# Base_Station_v3b.net
KiCad netlist of a schematic drawn in EAGLE
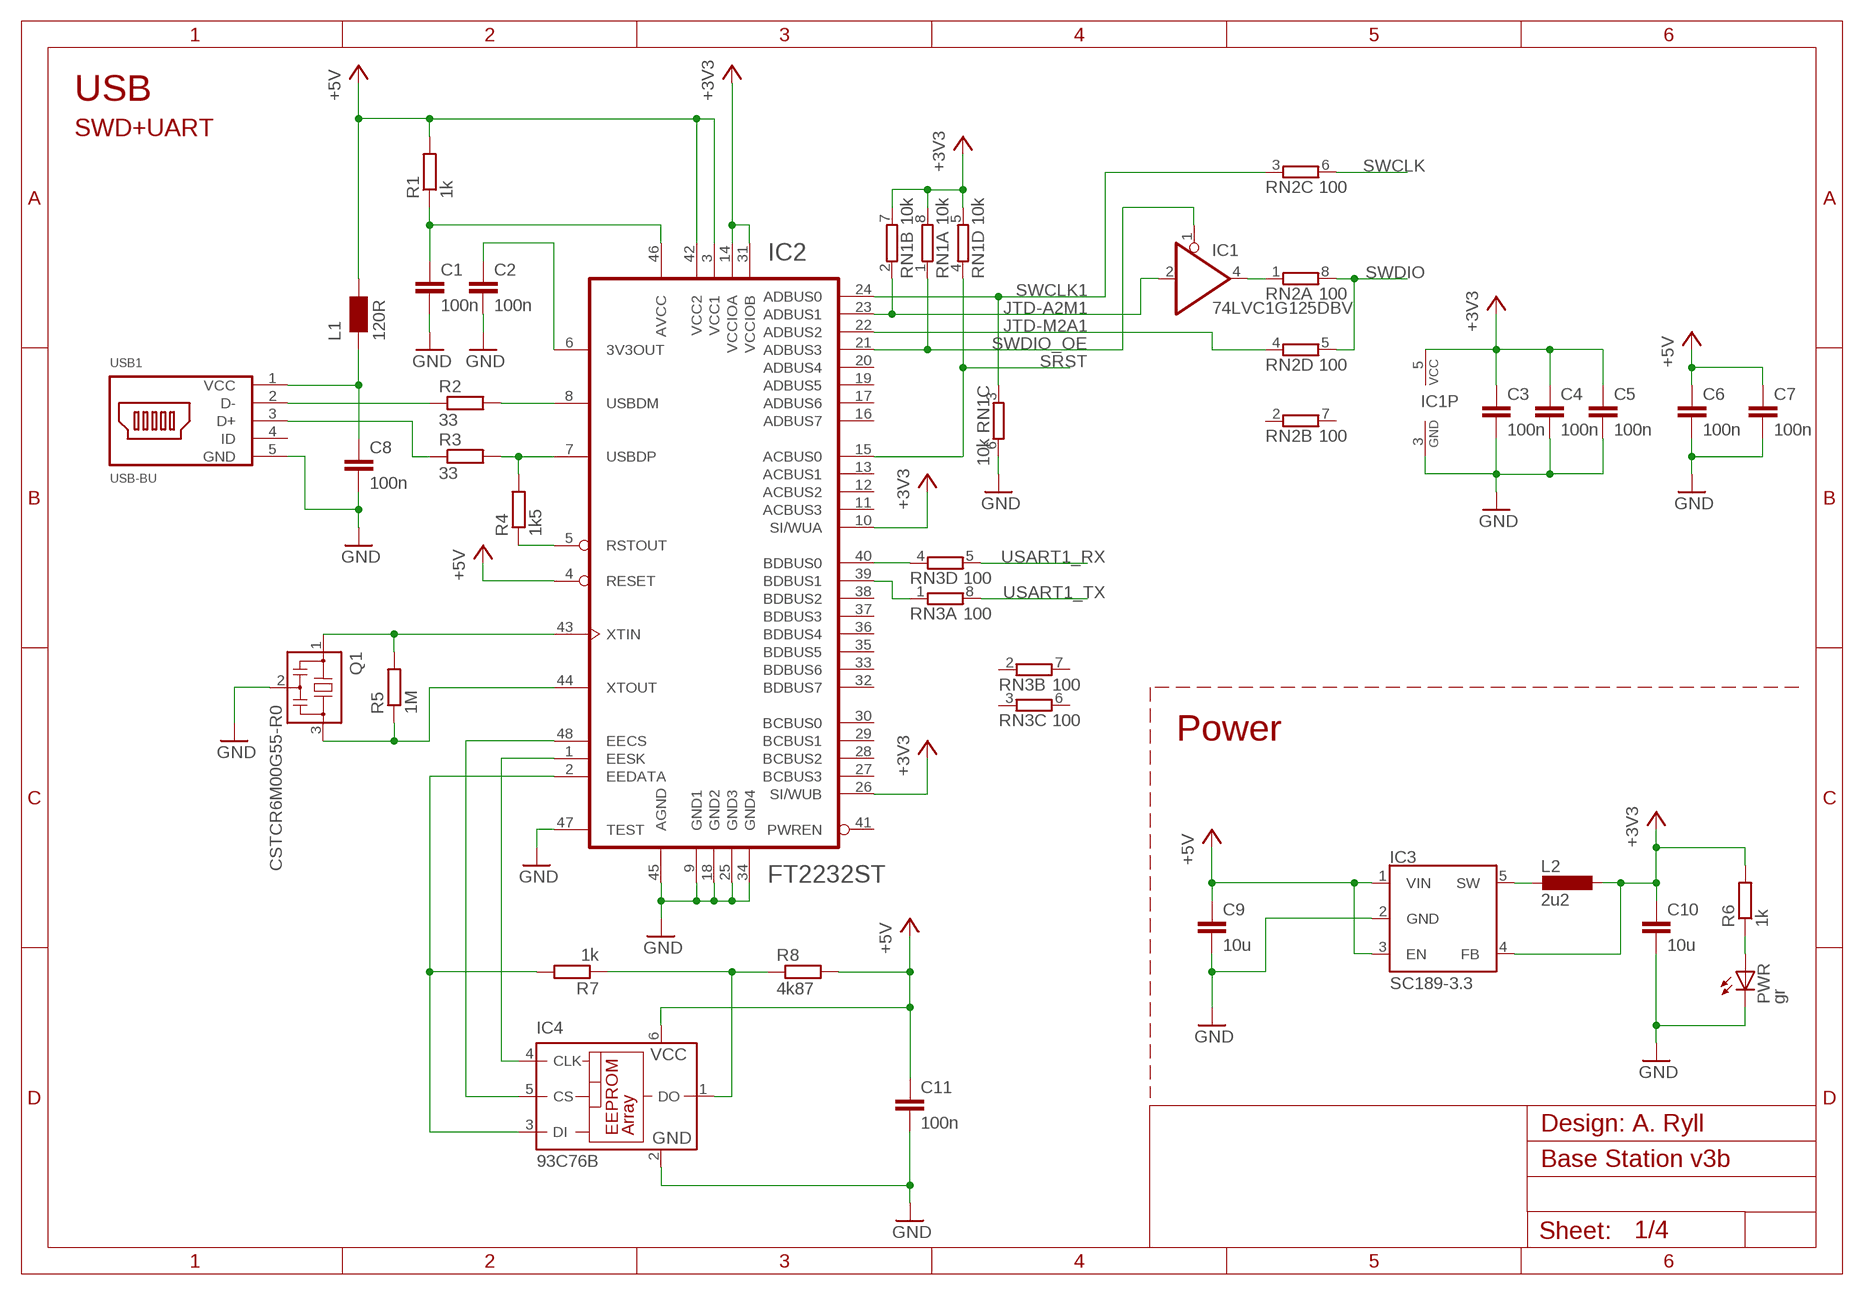
[diagram p0: schematic, sheet 1]
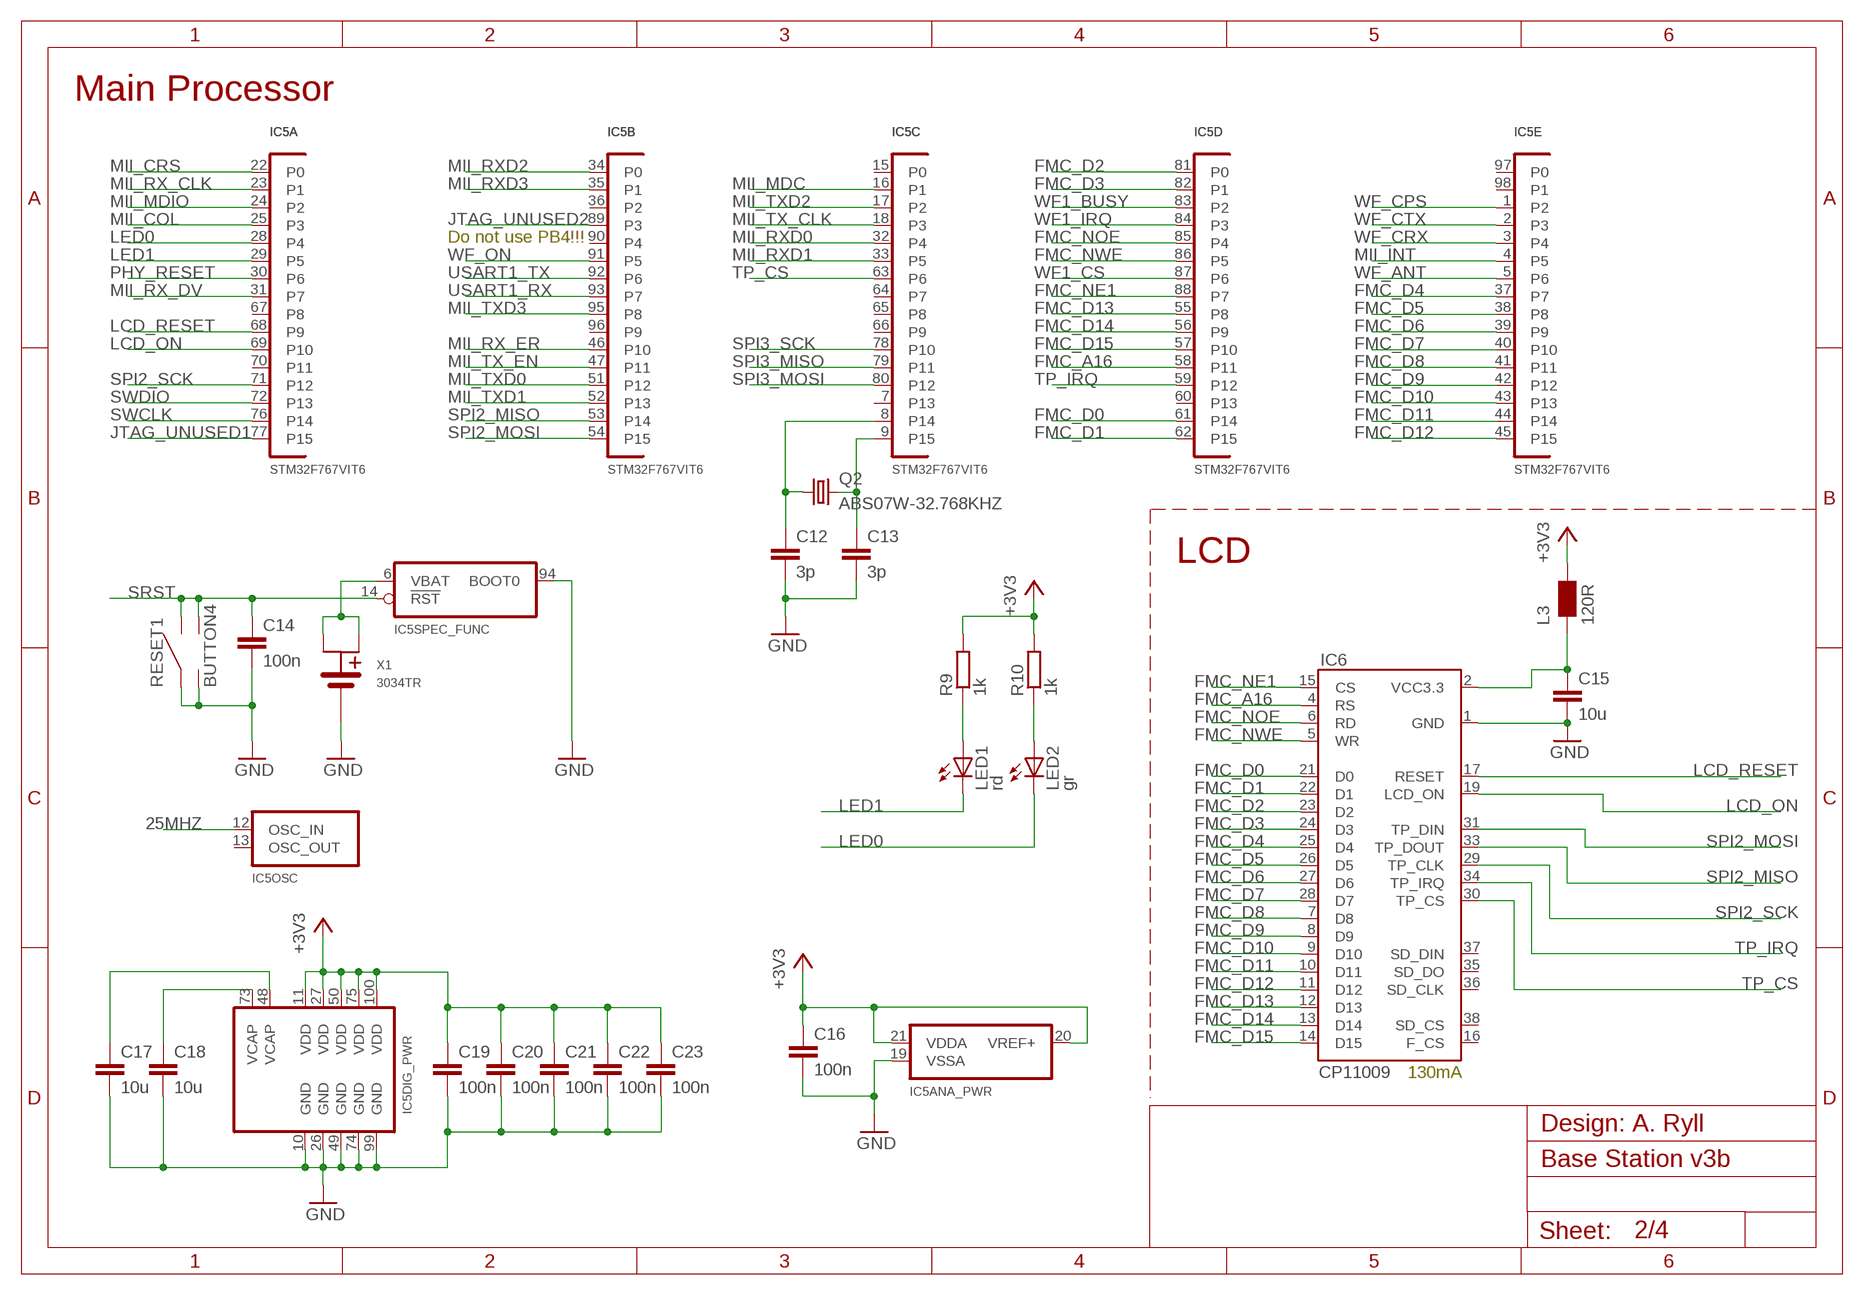
[diagram p1: schematic, sheet 2]
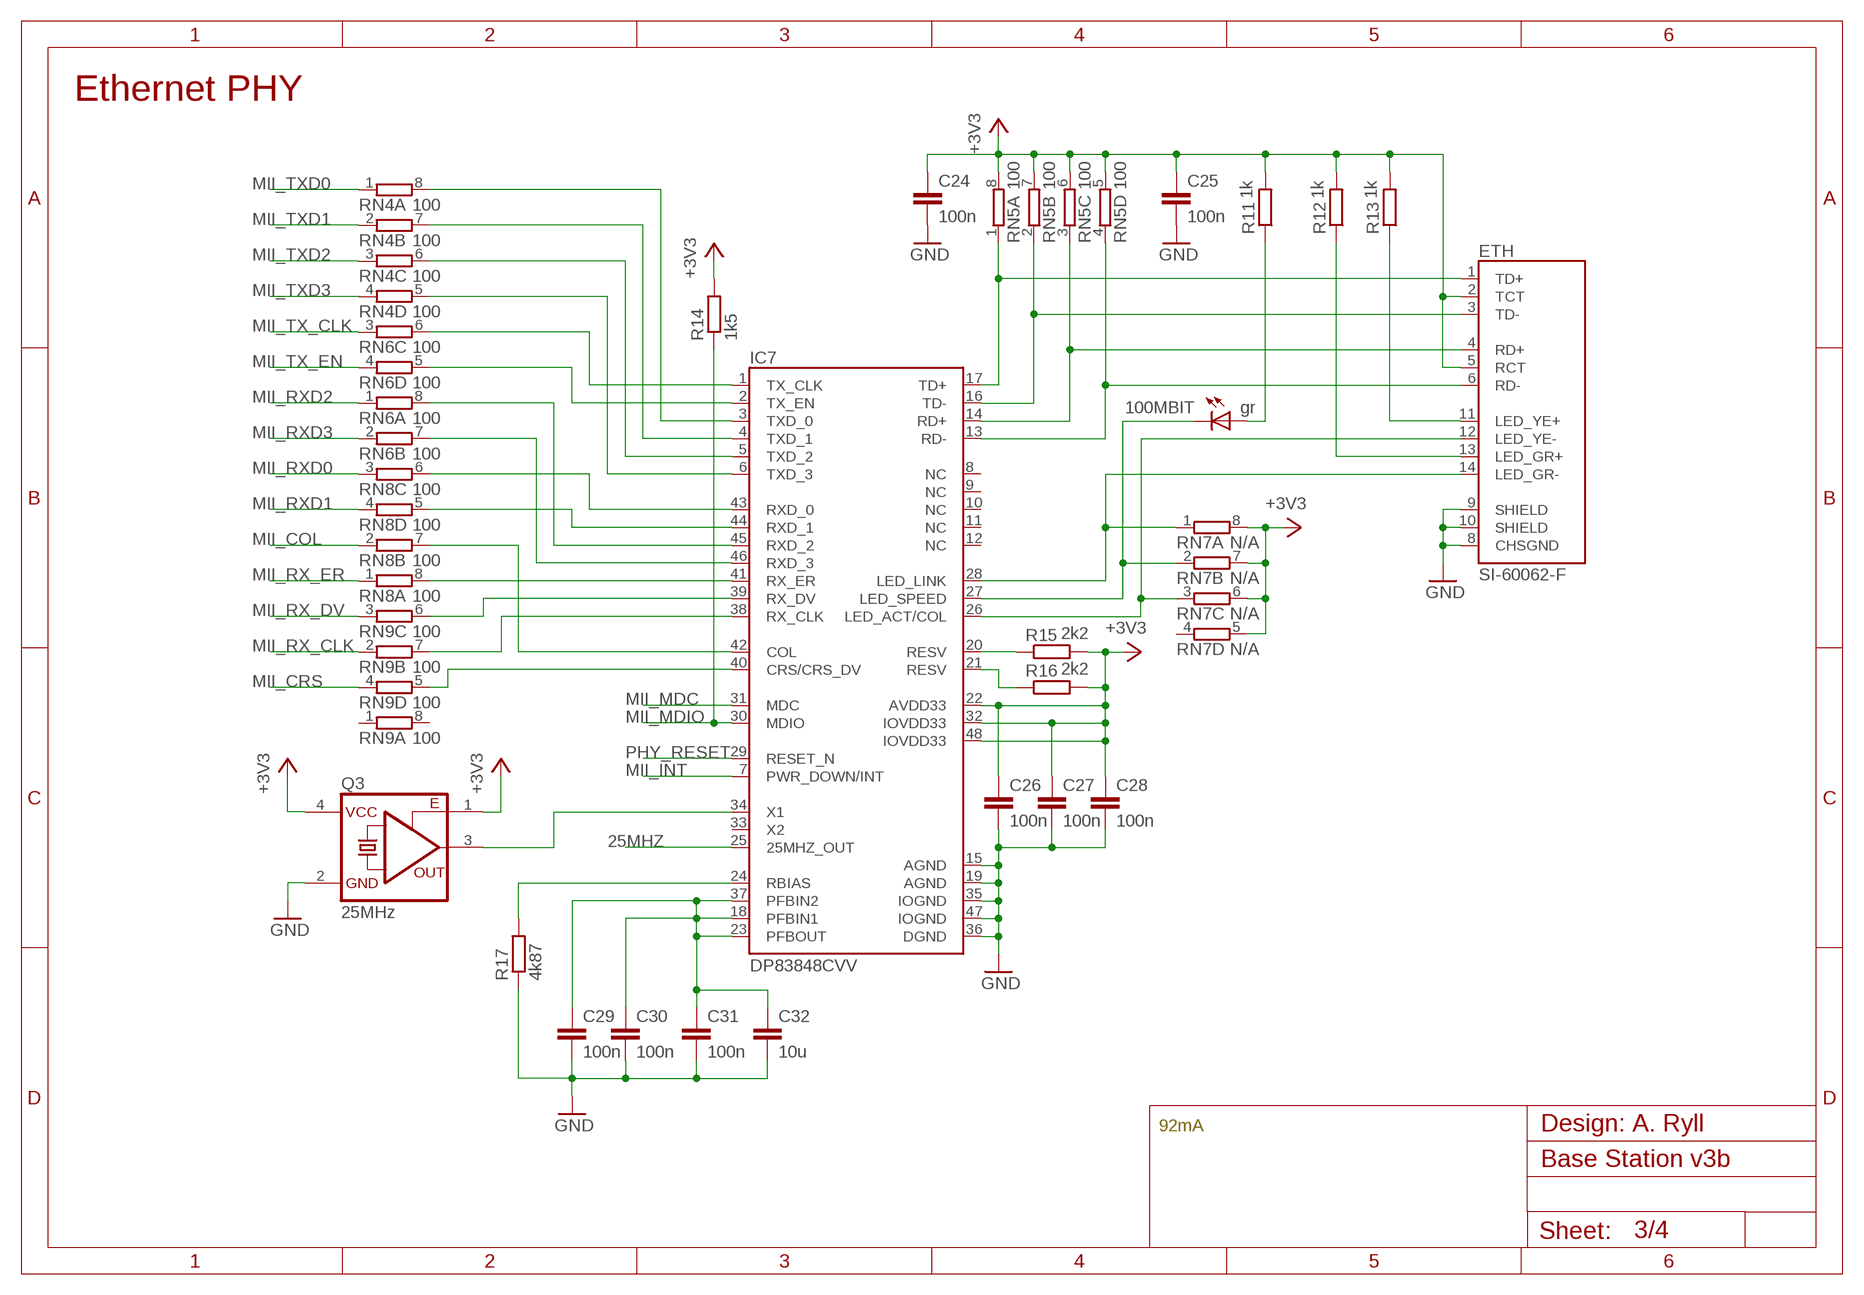
[diagram p2: schematic, sheet 3]
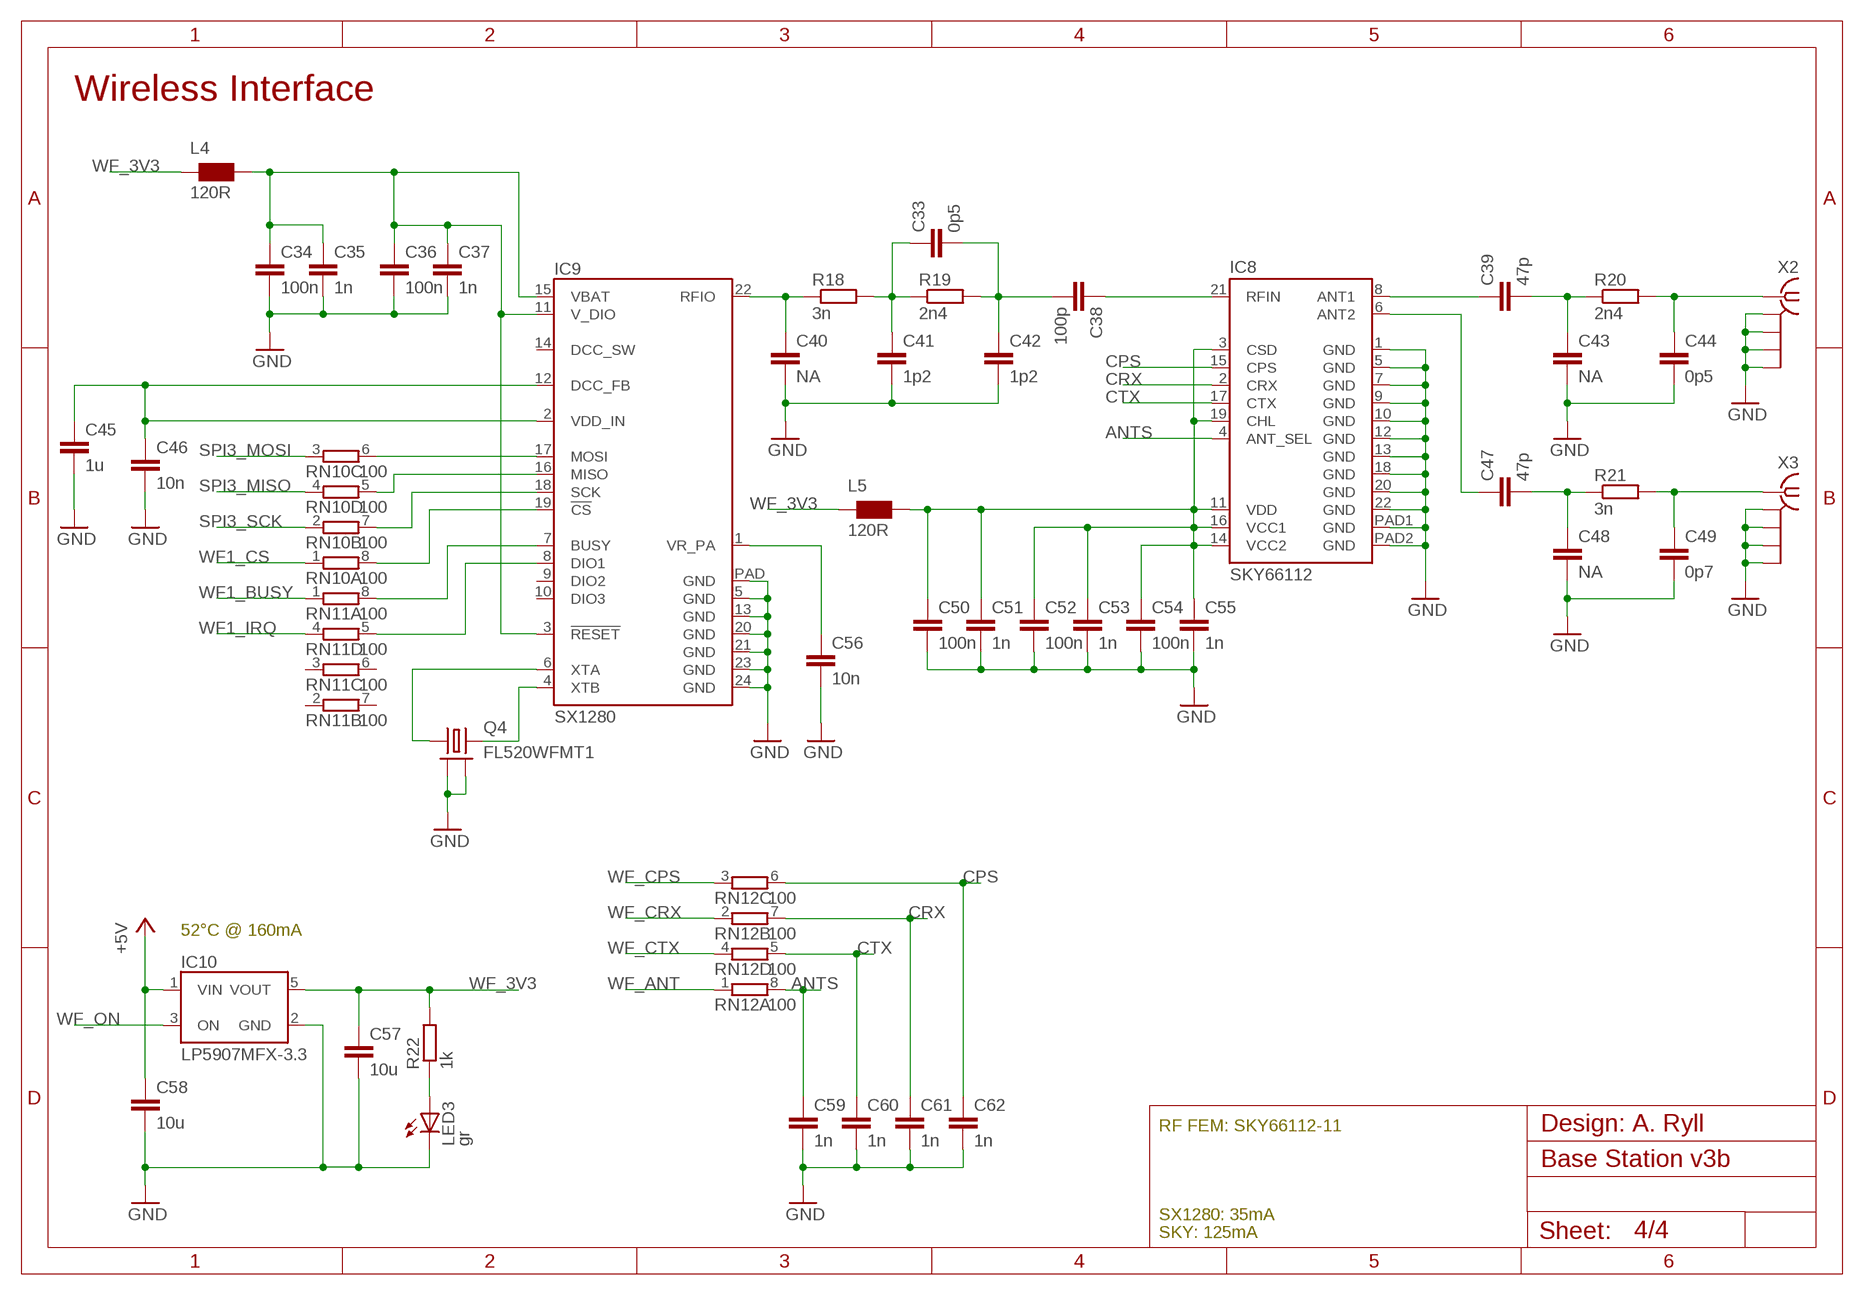
[diagram p3: schematic, sheet 4]

(export (version "E")
  (design (tool "Eeschema 10.0.6"))
  (components
    (comp (ref "C12")
      (value "3p")
      (footprint "eagle-import:C0603")
      (libsource (lib "eagle-import") (part "C-EUC0603"))
    )
    (comp (ref "C13")
      (value "3p")
      (footprint "eagle-import:C0603")
      (libsource (lib "eagle-import") (part "C-EUC0603"))
    )
    (comp (ref "C14")
      (value "100n")
      (footprint "eagle-import:C0603")
      (libsource (lib "eagle-import") (part "C-EUC0603"))
    )
    (comp (ref "C15")
      (value "10u")
      (footprint "eagle-import:C0603")
      (libsource (lib "eagle-import") (part "C-EUC0603"))
    )
    (comp (ref "C16")
      (value "100n")
      (footprint "eagle-import:C0603")
      (libsource (lib "eagle-import") (part "C-EUC0603"))
    )
    (comp (ref "C17")
      (value "10u")
      (footprint "eagle-import:C0603")
      (libsource (lib "eagle-import") (part "C-EUC0603"))
    )
    (comp (ref "C18")
      (value "10u")
      (footprint "eagle-import:C0603")
      (libsource (lib "eagle-import") (part "C-EUC0603"))
    )
    (comp (ref "C19")
      (value "100n")
      (footprint "eagle-import:C0603")
      (libsource (lib "eagle-import") (part "C-EUC0603"))
    )
    (comp (ref "C20")
      (value "100n")
      (footprint "eagle-import:C0603")
      (libsource (lib "eagle-import") (part "C-EUC0603"))
    )
    (comp (ref "C21")
      (value "100n")
      (footprint "eagle-import:C0603")
      (libsource (lib "eagle-import") (part "C-EUC0603"))
    )
    (comp (ref "C22")
      (value "100n")
      (footprint "eagle-import:C0603")
      (libsource (lib "eagle-import") (part "C-EUC0603"))
    )
    (comp (ref "C23")
      (value "100n")
      (footprint "eagle-import:C0603")
      (libsource (lib "eagle-import") (part "C-EUC0603"))
    )
    (comp (ref "IC5")
      (value "STM32F767VIT6")
      (footprint "eagle-import:LQFP100-ST")
      (libsource (lib "eagle-import") (part "STM32F76_V"))
    )
    (comp (ref "IC6")
      (value "CP11009")
      (footprint "eagle-import:CP11009-THX")
      (libsource (lib "eagle-import") (part "CP11009X"))
    )
    (comp (ref "L3")
      (value "120R")
      (footprint "eagle-import:0603")
      (libsource (lib "eagle-import") (part "WE-CBF_0603"))
    )
    (comp (ref "LED1")
      (value "rd")
      (footprint "eagle-import:CHIP-LED0603")
      (libsource (lib "eagle-import") (part "LEDCHIP-LED0603"))
    )
    (comp (ref "LED2")
      (value "gr")
      (footprint "eagle-import:CHIP-LED0603")
      (libsource (lib "eagle-import") (part "LEDCHIP-LED0603"))
    )
    (comp (ref "Q2")
      (value "ABS07W-32.768KHZ")
      (footprint "eagle-import:CRYSTAL-07W")
      (libsource (lib "eagle-import") (part "CRYSTAL07W"))
    )
    (comp (ref "R9")
      (value "1k")
      (footprint "eagle-import:R0603")
      (libsource (lib "eagle-import") (part "R-EU_R0603"))
    )
    (comp (ref "R10")
      (value "1k")
      (footprint "eagle-import:R0603")
      (libsource (lib "eagle-import") (part "R-EU_R0603"))
    )
    (comp (ref "RESET1")
      (value "BUTTON4")
      (footprint "eagle-import:BUTTON4")
      (libsource (lib "eagle-import") (part "BUTTON4"))
    )
    (comp (ref "X1")
      (value "3034TR")
      (footprint "eagle-import:CR2025")
      (libsource (lib "eagle-import") (part "BAT3"))
    )
    (comp (ref "C1")
      (value "100n")
      (footprint "eagle-import:C0603")
      (libsource (lib "eagle-import") (part "C-EUC0603"))
    )
    (comp (ref "C2")
      (value "100n")
      (footprint "eagle-import:C0603")
      (libsource (lib "eagle-import") (part "C-EUC0603"))
    )
    (comp (ref "C3")
      (value "100n")
      (footprint "eagle-import:C0603")
      (libsource (lib "eagle-import") (part "C-EUC0603"))
    )
    (comp (ref "C4")
      (value "100n")
      (footprint "eagle-import:C0603")
      (libsource (lib "eagle-import") (part "C-EUC0603"))
    )
    (comp (ref "C5")
      (value "100n")
      (footprint "eagle-import:C0603")
      (libsource (lib "eagle-import") (part "C-EUC0603"))
    )
    (comp (ref "C6")
      (value "100n")
      (footprint "eagle-import:C0603")
      (libsource (lib "eagle-import") (part "C-EUC0603"))
    )
    (comp (ref "C7")
      (value "100n")
      (footprint "eagle-import:C0603")
      (libsource (lib "eagle-import") (part "C-EUC0603"))
    )
    (comp (ref "C8")
      (value "100n")
      (footprint "eagle-import:C0603")
      (libsource (lib "eagle-import") (part "C-EUC0603"))
    )
    (comp (ref "C9")
      (value "10u")
      (footprint "eagle-import:C0603")
      (libsource (lib "eagle-import") (part "C-EUC0603"))
    )
    (comp (ref "C10")
      (value "10u")
      (footprint "eagle-import:C0603")
      (libsource (lib "eagle-import") (part "C-EUC0603"))
    )
    (comp (ref "C11")
      (value "100n")
      (footprint "eagle-import:C0603")
      (libsource (lib "eagle-import") (part "C-EUC0603"))
    )
    (comp (ref "IC1")
      (value "74LVC1G125DBV")
      (footprint "eagle-import:SOT23-5")
      (libsource (lib "eagle-import") (part "741G125DBVLVC"))
    )
    (comp (ref "IC2")
      (value "FT2232ST")
      (footprint "eagle-import:LQFP48-ST")
      (libsource (lib "eagle-import") (part "FT2232ST"))
    )
    (comp (ref "IC3")
      (value "SC189-3.3")
      (footprint "eagle-import:SOT23-5")
      (libsource (lib "eagle-import") (part "LM3671"))
    )
    (comp (ref "IC4")
      (value "93C76B")
      (footprint "eagle-import:SOT23-6")
      (libsource (lib "eagle-import") (part "9376?BC"))
    )
    (comp (ref "L1")
      (value "120R")
      (footprint "eagle-import:0603")
      (libsource (lib "eagle-import") (part "WE-CBF_0603"))
    )
    (comp (ref "L2")
      (value "2u2")
      (footprint "eagle-import:IHLP1616")
      (libsource (lib "eagle-import") (part "LIHLP"))
    )
    (comp (ref "PWR")
      (value "gr")
      (footprint "eagle-import:CHIP-LED0603")
      (libsource (lib "eagle-import") (part "LEDCHIP-LED0603"))
    )
    (comp (ref "Q1")
      (value "CSTCR6M00G55-R0")
      (footprint "eagle-import:CSTCR6M")
      (fields (field (name "MPN") "CSTCR6M00G53-R0"))
      (libsource (lib "eagle-import") (part "CSTCR6M00G53Z"))
    )
    (comp (ref "R1")
      (value "1k")
      (footprint "eagle-import:R0603")
      (libsource (lib "eagle-import") (part "R-EU_R0603"))
    )
    (comp (ref "R2")
      (value "33")
      (footprint "eagle-import:R0603")
      (libsource (lib "eagle-import") (part "R-EU_R0603"))
    )
    (comp (ref "R3")
      (value "33")
      (footprint "eagle-import:R0603")
      (libsource (lib "eagle-import") (part "R-EU_R0603"))
    )
    (comp (ref "R4")
      (value "1k5")
      (footprint "eagle-import:R0603")
      (libsource (lib "eagle-import") (part "R-EU_R0603"))
    )
    (comp (ref "R5")
      (value "1M")
      (footprint "eagle-import:R0603")
      (libsource (lib "eagle-import") (part "R-EU_R0603"))
    )
    (comp (ref "R6")
      (value "1k")
      (footprint "eagle-import:R0603")
      (libsource (lib "eagle-import") (part "R-EU_R0603"))
    )
    (comp (ref "R7")
      (value "1k")
      (footprint "eagle-import:R0603")
      (libsource (lib "eagle-import") (part "R-EU_R0603"))
    )
    (comp (ref "R8")
      (value "4k87")
      (footprint "eagle-import:R0603")
      (libsource (lib "eagle-import") (part "R-EU_R0603"))
    )
    (comp (ref "RN1")
      (value "10k")
      (footprint "eagle-import:EXB28V")
      (libsource (lib "eagle-import") (part "4R-NEXB28V"))
    )
    (comp (ref "RN2")
      (value "100")
      (footprint "eagle-import:EXB28V")
      (libsource (lib "eagle-import") (part "4R-NEXB28V"))
    )
    (comp (ref "RN3")
      (value "100")
      (footprint "eagle-import:EXB28V")
      (libsource (lib "eagle-import") (part "4R-NEXB28V"))
    )
    (comp (ref "USB1")
      (value "USB-BU")
      (footprint "eagle-import:USB-BMICRO")
      (libsource (lib "eagle-import") (part "USB-BU"))
    )
    (comp (ref "C33")
      (value "0p5")
      (footprint "eagle-import:C0402")
      (libsource (lib "eagle-import") (part "C-EUC0402"))
    )
    (comp (ref "C34")
      (value "100n")
      (footprint "eagle-import:C0603")
      (libsource (lib "eagle-import") (part "C-EUC0603"))
    )
    (comp (ref "C35")
      (value "1n")
      (footprint "eagle-import:C0603")
      (libsource (lib "eagle-import") (part "C-EUC0603"))
    )
    (comp (ref "C36")
      (value "100n")
      (footprint "eagle-import:C0603")
      (libsource (lib "eagle-import") (part "C-EUC0603"))
    )
    (comp (ref "C37")
      (value "1n")
      (footprint "eagle-import:C0603")
      (libsource (lib "eagle-import") (part "C-EUC0603"))
    )
    (comp (ref "C38")
      (value "100p")
      (footprint "eagle-import:C0402")
      (libsource (lib "eagle-import") (part "C-EUC0402"))
    )
    (comp (ref "C39")
      (value "47p")
      (footprint "eagle-import:C0402")
      (libsource (lib "eagle-import") (part "C-EUC0402"))
    )
    (comp (ref "C40")
      (value "NA")
      (footprint "eagle-import:C0402")
      (libsource (lib "eagle-import") (part "C-EUC0402"))
    )
    (comp (ref "C41")
      (value "1p2")
      (footprint "eagle-import:C0402")
      (libsource (lib "eagle-import") (part "C-EUC0402"))
    )
    (comp (ref "C42")
      (value "1p2")
      (footprint "eagle-import:C0402")
      (libsource (lib "eagle-import") (part "C-EUC0402"))
    )
    (comp (ref "C43")
      (value "NA")
      (footprint "eagle-import:C0402")
      (libsource (lib "eagle-import") (part "C-EUC0402"))
    )
    (comp (ref "C44")
      (value "0p5")
      (footprint "eagle-import:C0402")
      (libsource (lib "eagle-import") (part "C-EUC0402"))
    )
    (comp (ref "C45")
      (value "1u")
      (footprint "eagle-import:C0603")
      (libsource (lib "eagle-import") (part "C-EUC0603"))
    )
    (comp (ref "C46")
      (value "10n")
      (footprint "eagle-import:C0603")
      (libsource (lib "eagle-import") (part "C-EUC0603"))
    )
    (comp (ref "C47")
      (value "47p")
      (footprint "eagle-import:C0402")
      (libsource (lib "eagle-import") (part "C-EUC0402"))
    )
    (comp (ref "C48")
      (value "NA")
      (footprint "eagle-import:C0402")
      (libsource (lib "eagle-import") (part "C-EUC0402"))
    )
    (comp (ref "C49")
      (value "0p7")
      (footprint "eagle-import:C0402")
      (libsource (lib "eagle-import") (part "C-EUC0402"))
    )
    (comp (ref "C50")
      (value "100n")
      (footprint "eagle-import:C0603")
      (libsource (lib "eagle-import") (part "C-EUC0603"))
    )
    (comp (ref "C51")
      (value "1n")
      (footprint "eagle-import:C0603")
      (libsource (lib "eagle-import") (part "C-EUC0603"))
    )
    (comp (ref "C52")
      (value "100n")
      (footprint "eagle-import:C0603")
      (libsource (lib "eagle-import") (part "C-EUC0603"))
    )
    (comp (ref "C53")
      (value "1n")
      (footprint "eagle-import:C0603")
      (libsource (lib "eagle-import") (part "C-EUC0603"))
    )
    (comp (ref "C54")
      (value "100n")
      (footprint "eagle-import:C0603")
      (libsource (lib "eagle-import") (part "C-EUC0603"))
    )
    (comp (ref "C55")
      (value "1n")
      (footprint "eagle-import:C0603")
      (libsource (lib "eagle-import") (part "C-EUC0603"))
    )
    (comp (ref "C56")
      (value "10n")
      (footprint "eagle-import:C0603")
      (libsource (lib "eagle-import") (part "C-EUC0603"))
    )
    (comp (ref "C57")
      (value "10u")
      (footprint "eagle-import:C0603")
      (libsource (lib "eagle-import") (part "C-EUC0603"))
    )
    (comp (ref "C58")
      (value "10u")
      (footprint "eagle-import:C0603")
      (libsource (lib "eagle-import") (part "C-EUC0603"))
    )
    (comp (ref "C59")
      (value "1n")
      (footprint "eagle-import:C0603")
      (libsource (lib "eagle-import") (part "C-EUC0603"))
    )
    (comp (ref "C60")
      (value "1n")
      (footprint "eagle-import:C0603")
      (libsource (lib "eagle-import") (part "C-EUC0603"))
    )
    (comp (ref "C61")
      (value "1n")
      (footprint "eagle-import:C0603")
      (libsource (lib "eagle-import") (part "C-EUC0603"))
    )
    (comp (ref "C62")
      (value "1n")
      (footprint "eagle-import:C0603")
      (libsource (lib "eagle-import") (part "C-EUC0603"))
    )
    (comp (ref "IC8")
      (value "SKY66112")
      (footprint "eagle-import:SMCM-22")
      (libsource (lib "eagle-import") (part "SKY66112"))
    )
    (comp (ref "IC9")
      (value "SX1280")
      (footprint "eagle-import:QFN24L")
      (libsource (lib "eagle-import") (part "SX1280"))
    )
    (comp (ref "IC10")
      (value "LP5907MFX-3.3")
      (footprint "eagle-import:SOT23-5L")
      (libsource (lib "eagle-import") (part "LP2980"))
    )
    (comp (ref "L4")
      (value "120R")
      (footprint "eagle-import:0603")
      (libsource (lib "eagle-import") (part "WE-CBF_0603"))
    )
    (comp (ref "L5")
      (value "120R")
      (footprint "eagle-import:0603")
      (libsource (lib "eagle-import") (part "WE-CBF_0603"))
    )
    (comp (ref "LED3")
      (value "gr")
      (footprint "eagle-import:CHIP-LED0603")
      (libsource (lib "eagle-import") (part "LEDCHIP-LED0603"))
    )
    (comp (ref "Q4")
      (value "FL520WFMT1")
      (footprint "eagle-import:CRYSTAL-7M")
      (libsource (lib "eagle-import") (part "CRYSTAL47M"))
    )
    (comp (ref "R18")
      (value "3n")
      (footprint "eagle-import:R0402")
      (libsource (lib "eagle-import") (part "R-EU_R0402"))
    )
    (comp (ref "R19")
      (value "2n4")
      (footprint "eagle-import:R0402")
      (libsource (lib "eagle-import") (part "R-EU_R0402"))
    )
    (comp (ref "R20")
      (value "2n4")
      (footprint "eagle-import:R0402")
      (libsource (lib "eagle-import") (part "R-EU_R0402"))
    )
    (comp (ref "R21")
      (value "3n")
      (footprint "eagle-import:R0402")
      (libsource (lib "eagle-import") (part "R-EU_R0402"))
    )
    (comp (ref "R22")
      (value "1k")
      (footprint "eagle-import:R0603")
      (libsource (lib "eagle-import") (part "R-EU_R0603"))
    )
    (comp (ref "RN10")
      (value "100")
      (footprint "eagle-import:EXB28V")
      (libsource (lib "eagle-import") (part "4R-NEXB28V"))
    )
    (comp (ref "RN11")
      (value "100")
      (footprint "eagle-import:EXB28V")
      (libsource (lib "eagle-import") (part "4R-NEXB28V"))
    )
    (comp (ref "RN12")
      (value "100")
      (footprint "eagle-import:EXB28V")
      (libsource (lib "eagle-import") (part "4R-NEXB28V"))
    )
    (comp (ref "X2")
      (value "ANT-SMA-EDGERA")
      (footprint "eagle-import:ANT-SMA-RA")
      (libsource (lib "eagle-import") (part "ANT-SMA-EDGERA"))
    )
    (comp (ref "X3")
      (value "ANT-SMA-EDGERA")
      (footprint "eagle-import:ANT-SMA-RA")
      (libsource (lib "eagle-import") (part "ANT-SMA-EDGERA"))
    )
    (comp (ref "100MBIT")
      (value "gr")
      (footprint "eagle-import:CHIP-LED0603")
      (libsource (lib "eagle-import") (part "LEDCHIP-LED0603"))
    )
    (comp (ref "C24")
      (value "100n")
      (footprint "eagle-import:C0603")
      (libsource (lib "eagle-import") (part "C-EUC0603"))
    )
    (comp (ref "C25")
      (value "100n")
      (footprint "eagle-import:C0603")
      (libsource (lib "eagle-import") (part "C-EUC0603"))
    )
    (comp (ref "C26")
      (value "100n")
      (footprint "eagle-import:C0603")
      (libsource (lib "eagle-import") (part "C-EUC0603"))
    )
    (comp (ref "C27")
      (value "100n")
      (footprint "eagle-import:C0603")
      (libsource (lib "eagle-import") (part "C-EUC0603"))
    )
    (comp (ref "C28")
      (value "100n")
      (footprint "eagle-import:C0603")
      (libsource (lib "eagle-import") (part "C-EUC0603"))
    )
    (comp (ref "C29")
      (value "100n")
      (footprint "eagle-import:C0603")
      (libsource (lib "eagle-import") (part "C-EUC0603"))
    )
    (comp (ref "C30")
      (value "100n")
      (footprint "eagle-import:C0603")
      (libsource (lib "eagle-import") (part "C-EUC0603"))
    )
    (comp (ref "C31")
      (value "100n")
      (footprint "eagle-import:C0603")
      (libsource (lib "eagle-import") (part "C-EUC0603"))
    )
    (comp (ref "C32")
      (value "10u")
      (footprint "eagle-import:C0603")
      (libsource (lib "eagle-import") (part "C-EUC0603"))
    )
    (comp (ref "ETH")
      (value "SI-60062-F")
      (footprint "eagle-import:RJ45-LED")
      (libsource (lib "eagle-import") (part "RJ45-LED"))
    )
    (comp (ref "IC7")
      (value "DP83848CVV")
      (footprint "eagle-import:LQFP48")
      (libsource (lib "eagle-import") (part "DB8348C"))
    )
    (comp (ref "Q3")
      (value "25MHz")
      (footprint "eagle-import:7X")
      (libsource (lib "eagle-import") (part "OSCI7X"))
    )
    (comp (ref "R11")
      (value "1k")
      (footprint "eagle-import:R0603")
      (libsource (lib "eagle-import") (part "R-EU_R0603"))
    )
    (comp (ref "R12")
      (value "1k")
      (footprint "eagle-import:R0603")
      (libsource (lib "eagle-import") (part "R-EU_R0603"))
    )
    (comp (ref "R13")
      (value "1k")
      (footprint "eagle-import:R0603")
      (libsource (lib "eagle-import") (part "R-EU_R0603"))
    )
    (comp (ref "R14")
      (value "1k5")
      (footprint "eagle-import:R0603")
      (libsource (lib "eagle-import") (part "R-EU_R0603"))
    )
    (comp (ref "R15")
      (value "2k2")
      (footprint "eagle-import:R0603")
      (libsource (lib "eagle-import") (part "R-EU_R0603"))
    )
    (comp (ref "R16")
      (value "2k2")
      (footprint "eagle-import:R0603")
      (libsource (lib "eagle-import") (part "R-EU_R0603"))
    )
    (comp (ref "R17")
      (value "4k87")
      (footprint "eagle-import:R0603")
      (libsource (lib "eagle-import") (part "R-EU_R0603"))
    )
    (comp (ref "RN4")
      (value "100")
      (footprint "eagle-import:EXB28V")
      (libsource (lib "eagle-import") (part "4R-NEXB28V"))
    )
    (comp (ref "RN5")
      (value "100")
      (footprint "eagle-import:EXB28V")
      (libsource (lib "eagle-import") (part "4R-NEXB28V"))
    )
    (comp (ref "RN6")
      (value "100")
      (footprint "eagle-import:EXB28V")
      (libsource (lib "eagle-import") (part "4R-NEXB28V"))
    )
    (comp (ref "RN7")
      (value "N/A")
      (footprint "eagle-import:EXB28V")
      (libsource (lib "eagle-import") (part "4R-NEXB28V"))
    )
    (comp (ref "RN8")
      (value "100")
      (footprint "eagle-import:EXB28V")
      (libsource (lib "eagle-import") (part "4R-NEXB28V"))
    )
    (comp (ref "RN9")
      (value "100")
      (footprint "eagle-import:EXB28V")
      (libsource (lib "eagle-import") (part "4R-NEXB28V"))
    )
  )
  (nets
    (net (code "1") (name "+3V3") (class "Default")
      (node (ref "C10") (pin "1") (pinfunction "1_1") (pintype "passive"))
      (node (ref "C16") (pin "1") (pinfunction "1_1") (pintype "passive"))
      (node (ref "C19") (pin "1") (pinfunction "1_1") (pintype "passive"))
      (node (ref "C20") (pin "1") (pinfunction "1_1") (pintype "passive"))
      (node (ref "C21") (pin "1") (pinfunction "1_1") (pintype "passive"))
      (node (ref "C22") (pin "1") (pinfunction "1_1") (pintype "passive"))
      (node (ref "C23") (pin "1") (pinfunction "1_1") (pintype "passive"))
      (node (ref "C24") (pin "1") (pinfunction "1_1") (pintype "passive"))
      (node (ref "C25") (pin "1") (pinfunction "1_1") (pintype "passive"))
      (node (ref "C26") (pin "1") (pinfunction "1_1") (pintype "passive"))
      (node (ref "C27") (pin "1") (pinfunction "1_1") (pintype "passive"))
      (node (ref "C28") (pin "1") (pinfunction "1_1") (pintype "passive"))
      (node (ref "C3") (pin "1") (pinfunction "1_1") (pintype "passive"))
      (node (ref "C4") (pin "1") (pinfunction "1_1") (pintype "passive"))
      (node (ref "C5") (pin "1") (pinfunction "1_1") (pintype "passive"))
      (node (ref "ETH") (pin "2") (pinfunction "TCT_2") (pintype "bidirectional"))
      (node (ref "ETH") (pin "5") (pinfunction "RCT_5") (pintype "bidirectional"))
      (node (ref "IC1") (pin "5") (pinfunction "VCC_5") (pintype "power_in"))
      (node (ref "IC2") (pin "10") (pinfunction "SI/WUA_10") (pintype "bidirectional"))
      (node (ref "IC2") (pin "14") (pinfunction "VCCIOA_14") (pintype "bidirectional"))
      (node (ref "IC2") (pin "26") (pinfunction "SI/WUB_26") (pintype "bidirectional"))
      (node (ref "IC2") (pin "31") (pinfunction "VCCIOB_31") (pintype "bidirectional"))
      (node (ref "IC3") (pin "4") (pinfunction "FB_4") (pintype "bidirectional"))
      (node (ref "IC5") (pin "100") (pinfunction "VDD_100") (pintype "power_in"))
      (node (ref "IC5") (pin "11") (pinfunction "VDD_11") (pintype "power_in"))
      (node (ref "IC5") (pin "20") (pinfunction "VREF+_20") (pintype "passive"))
      (node (ref "IC5") (pin "21") (pinfunction "VDDA_21") (pintype "power_in"))
      (node (ref "IC5") (pin "27") (pinfunction "VDD_27") (pintype "power_in"))
      (node (ref "IC5") (pin "50") (pinfunction "VDD_50") (pintype "power_in"))
      (node (ref "IC5") (pin "75") (pinfunction "VDD_75") (pintype "power_in"))
      (node (ref "IC7") (pin "22") (pinfunction "AVDD33_22") (pintype "bidirectional"))
      (node (ref "IC7") (pin "32") (pinfunction "IOVDD33_32") (pintype "bidirectional"))
      (node (ref "IC7") (pin "48") (pinfunction "IOVDD33_48") (pintype "bidirectional"))
      (node (ref "L2") (pin "P$1") (pinfunction "1_P$1") (pintype "passive"))
      (node (ref "L3") (pin "2") (pinfunction "2_2") (pintype "passive"))
      (node (ref "Q3") (pin "1") (pinfunction "OE_1") (pintype "input"))
      (node (ref "Q3") (pin "4") (pinfunction "VCC_4") (pintype "power_in"))
      (node (ref "R10") (pin "2") (pinfunction "2_2") (pintype "passive"))
      (node (ref "R11") (pin "2") (pinfunction "2_2") (pintype "passive"))
      (node (ref "R12") (pin "2") (pinfunction "2_2") (pintype "passive"))
      (node (ref "R13") (pin "2") (pinfunction "2_2") (pintype "passive"))
      (node (ref "R14") (pin "2") (pinfunction "2_2") (pintype "passive"))
      (node (ref "R15") (pin "2") (pinfunction "2_2") (pintype "passive"))
      (node (ref "R16") (pin "2") (pinfunction "2_2") (pintype "passive"))
      (node (ref "R6") (pin "2") (pinfunction "2_2") (pintype "passive"))
      (node (ref "R9") (pin "2") (pinfunction "2_2") (pintype "passive"))
      (node (ref "RN1") (pin "5") (pinfunction "2_5") (pintype "passive"))
      (node (ref "RN1") (pin "7") (pinfunction "2_7") (pintype "passive"))
      (node (ref "RN1") (pin "8") (pinfunction "2_8") (pintype "passive"))
      (node (ref "RN5") (pin "5") (pinfunction "2_5") (pintype "passive"))
      (node (ref "RN5") (pin "6") (pinfunction "2_6") (pintype "passive"))
      (node (ref "RN5") (pin "7") (pinfunction "2_7") (pintype "passive"))
      (node (ref "RN5") (pin "8") (pinfunction "2_8") (pintype "passive"))
      (node (ref "RN7") (pin "5") (pinfunction "2_5") (pintype "passive"))
      (node (ref "RN7") (pin "6") (pinfunction "2_6") (pintype "passive"))
      (node (ref "RN7") (pin "7") (pinfunction "2_7") (pintype "passive"))
      (node (ref "RN7") (pin "8") (pinfunction "2_8") (pintype "passive"))
    )
    (net (code "2") (name "+5V") (class "Default")
      (node (ref "C11") (pin "1") (pinfunction "1_1") (pintype "passive"))
      (node (ref "C58") (pin "1") (pinfunction "1_1") (pintype "passive"))
      (node (ref "C6") (pin "1") (pinfunction "1_1") (pintype "passive"))
      (node (ref "C7") (pin "1") (pinfunction "1_1") (pintype "passive"))
      (node (ref "C9") (pin "1") (pinfunction "1_1") (pintype "passive"))
      (node (ref "IC10") (pin "1") (pinfunction "VIN_1") (pintype "passive"))
      (node (ref "IC2") (pin "3") (pinfunction "VCC1_3") (pintype "bidirectional"))
      (node (ref "IC2") (pin "4") (pinfunction "RESET_4") (pintype "bidirectional"))
      (node (ref "IC2") (pin "42") (pinfunction "VCC2_42") (pintype "bidirectional"))
      (node (ref "IC3") (pin "1") (pinfunction "VIN_1") (pintype "bidirectional"))
      (node (ref "IC3") (pin "3") (pinfunction "EN_3") (pintype "bidirectional"))
      (node (ref "IC4") (pin "6") (pinfunction "VCC_6") (pintype "power_in"))
      (node (ref "L1") (pin "2") (pinfunction "2_2") (pintype "passive"))
      (node (ref "R1") (pin "2") (pinfunction "2_2") (pintype "passive"))
      (node (ref "R8") (pin "2") (pinfunction "2_2") (pintype "passive"))
    )
    (net (code "3") (name "25MHZ") (class "Default")
      (node (ref "IC5") (pin "12") (pinfunction "OSC_IN_12") (pintype "passive"))
      (node (ref "IC7") (pin "25") (pinfunction "25MHZ_OUT_25") (pintype "bidirectional"))
    )
    (net (code "4") (name "ANTS") (class "Default")
      (node (ref "C59") (pin "1") (pinfunction "1_1") (pintype "passive"))
      (node (ref "IC8") (pin "4") (pinfunction "ANT_SEL_4") (pintype "bidirectional"))
      (node (ref "RN12") (pin "8") (pinfunction "2_8") (pintype "passive"))
    )
    (net (code "5") (name "CPS") (class "Default")
      (node (ref "C62") (pin "1") (pinfunction "1_1") (pintype "passive"))
      (node (ref "IC8") (pin "15") (pinfunction "CPS_15") (pintype "bidirectional"))
      (node (ref "RN12") (pin "6") (pinfunction "2_6") (pintype "passive"))
    )
    (net (code "6") (name "CRX") (class "Default")
      (node (ref "C61") (pin "1") (pinfunction "1_1") (pintype "passive"))
      (node (ref "IC8") (pin "2") (pinfunction "CRX_2") (pintype "bidirectional"))
      (node (ref "RN12") (pin "7") (pinfunction "2_7") (pintype "passive"))
    )
    (net (code "7") (name "CTX") (class "Default")
      (node (ref "C60") (pin "1") (pinfunction "1_1") (pintype "passive"))
      (node (ref "IC8") (pin "17") (pinfunction "CTX_17") (pintype "bidirectional"))
      (node (ref "RN12") (pin "5") (pinfunction "2_5") (pintype "passive"))
    )
    (net (code "8") (name "FMC_A16") (class "Default")
      (node (ref "IC5") (pin "58") (pinfunction "P11_58") (pintype "bidirectional"))
      (node (ref "IC6") (pin "4") (pinfunction "RS_4") (pintype "bidirectional"))
    )
    (net (code "9") (name "FMC_D0") (class "Default")
      (node (ref "IC5") (pin "61") (pinfunction "P14_61") (pintype "bidirectional"))
      (node (ref "IC6") (pin "21") (pinfunction "D0_21") (pintype "bidirectional"))
    )
    (net (code "10") (name "FMC_D1") (class "Default")
      (node (ref "IC5") (pin "62") (pinfunction "P15_62") (pintype "bidirectional"))
      (node (ref "IC6") (pin "22") (pinfunction "D1_22") (pintype "bidirectional"))
    )
    (net (code "11") (name "FMC_D2") (class "Default")
      (node (ref "IC5") (pin "81") (pinfunction "P0_81") (pintype "bidirectional"))
      (node (ref "IC6") (pin "23") (pinfunction "D2_23") (pintype "bidirectional"))
    )
    (net (code "12") (name "FMC_D3") (class "Default")
      (node (ref "IC5") (pin "82") (pinfunction "P1_82") (pintype "bidirectional"))
      (node (ref "IC6") (pin "24") (pinfunction "D3_24") (pintype "bidirectional"))
    )
    (net (code "13") (name "FMC_D4") (class "Default")
      (node (ref "IC5") (pin "37") (pinfunction "P7_37") (pintype "bidirectional"))
      (node (ref "IC6") (pin "25") (pinfunction "D4_25") (pintype "bidirectional"))
    )
    (net (code "14") (name "FMC_D5") (class "Default")
      (node (ref "IC5") (pin "38") (pinfunction "P8_38") (pintype "bidirectional"))
      (node (ref "IC6") (pin "26") (pinfunction "D5_26") (pintype "bidirectional"))
    )
    (net (code "15") (name "FMC_D6") (class "Default")
      (node (ref "IC5") (pin "39") (pinfunction "P9_39") (pintype "bidirectional"))
      (node (ref "IC6") (pin "27") (pinfunction "D6_27") (pintype "bidirectional"))
    )
    (net (code "16") (name "FMC_D7") (class "Default")
      (node (ref "IC5") (pin "40") (pinfunction "P10_40") (pintype "bidirectional"))
      (node (ref "IC6") (pin "28") (pinfunction "D7_28") (pintype "bidirectional"))
    )
    (net (code "17") (name "FMC_D8") (class "Default")
      (node (ref "IC5") (pin "41") (pinfunction "P11_41") (pintype "bidirectional"))
      (node (ref "IC6") (pin "7") (pinfunction "D8_7") (pintype "bidirectional"))
    )
    (net (code "18") (name "FMC_D9") (class "Default")
      (node (ref "IC5") (pin "42") (pinfunction "P12_42") (pintype "bidirectional"))
      (node (ref "IC6") (pin "8") (pinfunction "D9_8") (pintype "bidirectional"))
    )
    (net (code "19") (name "FMC_D10") (class "Default")
      (node (ref "IC5") (pin "43") (pinfunction "P13_43") (pintype "bidirectional"))
      (node (ref "IC6") (pin "9") (pinfunction "D10_9") (pintype "bidirectional"))
    )
    (net (code "20") (name "FMC_D11") (class "Default")
      (node (ref "IC5") (pin "44") (pinfunction "P14_44") (pintype "bidirectional"))
      (node (ref "IC6") (pin "10") (pinfunction "D11_10") (pintype "bidirectional"))
    )
    (net (code "21") (name "FMC_D12") (class "Default")
      (node (ref "IC5") (pin "45") (pinfunction "P15_45") (pintype "bidirectional"))
      (node (ref "IC6") (pin "11") (pinfunction "D12_11") (pintype "bidirectional"))
    )
    (net (code "22") (name "FMC_D13") (class "Default")
      (node (ref "IC5") (pin "55") (pinfunction "P8_55") (pintype "bidirectional"))
      (node (ref "IC6") (pin "12") (pinfunction "D13_12") (pintype "bidirectional"))
    )
    (net (code "23") (name "FMC_D14") (class "Default")
      (node (ref "IC5") (pin "56") (pinfunction "P9_56") (pintype "bidirectional"))
      (node (ref "IC6") (pin "13") (pinfunction "D14_13") (pintype "bidirectional"))
    )
    (net (code "24") (name "FMC_D15") (class "Default")
      (node (ref "IC5") (pin "57") (pinfunction "P10_57") (pintype "bidirectional"))
      (node (ref "IC6") (pin "14") (pinfunction "D15_14") (pintype "bidirectional"))
    )
    (net (code "25") (name "FMC_NE1") (class "Default")
      (node (ref "IC5") (pin "88") (pinfunction "P7_88") (pintype "bidirectional"))
      (node (ref "IC6") (pin "15") (pinfunction "CS_15") (pintype "bidirectional"))
    )
    (net (code "26") (name "FMC_NOE") (class "Default")
      (node (ref "IC5") (pin "85") (pinfunction "P4_85") (pintype "bidirectional"))
      (node (ref "IC6") (pin "6") (pinfunction "RD_6") (pintype "bidirectional"))
    )
    (net (code "27") (name "FMC_NWE") (class "Default")
      (node (ref "IC5") (pin "86") (pinfunction "P5_86") (pintype "bidirectional"))
      (node (ref "IC6") (pin "5") (pinfunction "WR_5") (pintype "bidirectional"))
    )
    (net (code "28") (name "GND") (class "Default")
      (node (ref "C1") (pin "2") (pinfunction "2_2") (pintype "passive"))
      (node (ref "C10") (pin "2") (pinfunction "2_2") (pintype "passive"))
      (node (ref "C11") (pin "2") (pinfunction "2_2") (pintype "passive"))
      (node (ref "C12") (pin "2") (pinfunction "2_2") (pintype "passive"))
      (node (ref "C13") (pin "2") (pinfunction "2_2") (pintype "passive"))
      (node (ref "C14") (pin "2") (pinfunction "2_2") (pintype "passive"))
      (node (ref "C15") (pin "2") (pinfunction "2_2") (pintype "passive"))
      (node (ref "C16") (pin "2") (pinfunction "2_2") (pintype "passive"))
      (node (ref "C17") (pin "2") (pinfunction "2_2") (pintype "passive"))
      (node (ref "C18") (pin "2") (pinfunction "2_2") (pintype "passive"))
      (node (ref "C19") (pin "2") (pinfunction "2_2") (pintype "passive"))
      (node (ref "C2") (pin "2") (pinfunction "2_2") (pintype "passive"))
      (node (ref "C20") (pin "2") (pinfunction "2_2") (pintype "passive"))
      (node (ref "C21") (pin "2") (pinfunction "2_2") (pintype "passive"))
      (node (ref "C22") (pin "2") (pinfunction "2_2") (pintype "passive"))
      (node (ref "C23") (pin "2") (pinfunction "2_2") (pintype "passive"))
      (node (ref "C24") (pin "2") (pinfunction "2_2") (pintype "passive"))
      (node (ref "C25") (pin "2") (pinfunction "2_2") (pintype "passive"))
      (node (ref "C26") (pin "2") (pinfunction "2_2") (pintype "passive"))
      (node (ref "C27") (pin "2") (pinfunction "2_2") (pintype "passive"))
      (node (ref "C28") (pin "2") (pinfunction "2_2") (pintype "passive"))
      (node (ref "C29") (pin "2") (pinfunction "2_2") (pintype "passive"))
      (node (ref "C3") (pin "2") (pinfunction "2_2") (pintype "passive"))
      (node (ref "C30") (pin "2") (pinfunction "2_2") (pintype "passive"))
      (node (ref "C31") (pin "2") (pinfunction "2_2") (pintype "passive"))
      (node (ref "C32") (pin "2") (pinfunction "2_2") (pintype "passive"))
      (node (ref "C34") (pin "2") (pinfunction "2_2") (pintype "passive"))
      (node (ref "C35") (pin "2") (pinfunction "2_2") (pintype "passive"))
      (node (ref "C36") (pin "2") (pinfunction "2_2") (pintype "passive"))
      (node (ref "C37") (pin "2") (pinfunction "2_2") (pintype "passive"))
      (node (ref "C4") (pin "2") (pinfunction "2_2") (pintype "passive"))
      (node (ref "C40") (pin "2") (pinfunction "2_2") (pintype "passive"))
      (node (ref "C41") (pin "2") (pinfunction "2_2") (pintype "passive"))
      (node (ref "C42") (pin "2") (pinfunction "2_2") (pintype "passive"))
      (node (ref "C43") (pin "2") (pinfunction "2_2") (pintype "passive"))
      (node (ref "C44") (pin "2") (pinfunction "2_2") (pintype "passive"))
      (node (ref "C45") (pin "2") (pinfunction "2_2") (pintype "passive"))
      (node (ref "C46") (pin "2") (pinfunction "2_2") (pintype "passive"))
      (node (ref "C48") (pin "2") (pinfunction "2_2") (pintype "passive"))
      (node (ref "C49") (pin "2") (pinfunction "2_2") (pintype "passive"))
      (node (ref "C5") (pin "2") (pinfunction "2_2") (pintype "passive"))
      (node (ref "C50") (pin "2") (pinfunction "2_2") (pintype "passive"))
      (node (ref "C51") (pin "2") (pinfunction "2_2") (pintype "passive"))
      (node (ref "C52") (pin "2") (pinfunction "2_2") (pintype "passive"))
      (node (ref "C53") (pin "2") (pinfunction "2_2") (pintype "passive"))
      (node (ref "C54") (pin "2") (pinfunction "2_2") (pintype "passive"))
      (node (ref "C55") (pin "2") (pinfunction "2_2") (pintype "passive"))
      (node (ref "C56") (pin "2") (pinfunction "2_2") (pintype "passive"))
      (node (ref "C57") (pin "2") (pinfunction "2_2") (pintype "passive"))
      (node (ref "C58") (pin "2") (pinfunction "2_2") (pintype "passive"))
      (node (ref "C59") (pin "2") (pinfunction "2_2") (pintype "passive"))
      (node (ref "C6") (pin "2") (pinfunction "2_2") (pintype "passive"))
      (node (ref "C60") (pin "2") (pinfunction "2_2") (pintype "passive"))
      (node (ref "C61") (pin "2") (pinfunction "2_2") (pintype "passive"))
      (node (ref "C62") (pin "2") (pinfunction "2_2") (pintype "passive"))
      (node (ref "C7") (pin "2") (pinfunction "2_2") (pintype "passive"))
      (node (ref "C8") (pin "2") (pinfunction "2_2") (pintype "passive"))
      (node (ref "C9") (pin "2") (pinfunction "2_2") (pintype "passive"))
      (node (ref "ETH") (pin "10") (pinfunction "SHIELD_10") (pintype "bidirectional"))
      (node (ref "ETH") (pin "8") (pinfunction "CHSGND_8") (pintype "bidirectional"))
      (node (ref "ETH") (pin "9") (pinfunction "SHIELD_9") (pintype "bidirectional"))
      (node (ref "IC1") (pin "3") (pinfunction "GND_3") (pintype "power_in"))
      (node (ref "IC10") (pin "2") (pinfunction "GND_2") (pintype "power_in"))
      (node (ref "IC2") (pin "18") (pinfunction "GND2_18") (pintype "bidirectional"))
      (node (ref "IC2") (pin "25") (pinfunction "GND3_25") (pintype "bidirectional"))
      (node (ref "IC2") (pin "34") (pinfunction "GND4_34") (pintype "bidirectional"))
      (node (ref "IC2") (pin "45") (pinfunction "AGND_45") (pintype "bidirectional"))
      (node (ref "IC2") (pin "47") (pinfunction "TEST_47") (pintype "bidirectional"))
      (node (ref "IC2") (pin "9") (pinfunction "GND1_9") (pintype "bidirectional"))
      (node (ref "IC3") (pin "2") (pinfunction "GND_2") (pintype "bidirectional"))
      (node (ref "IC4") (pin "2") (pinfunction "GND_2") (pintype "power_in"))
      (node (ref "IC5") (pin "10") (pinfunction "GND_10") (pintype "power_in"))
      (node (ref "IC5") (pin "19") (pinfunction "VSSA_19") (pintype "power_in"))
      (node (ref "IC5") (pin "26") (pinfunction "GND_26") (pintype "power_in"))
      (node (ref "IC5") (pin "49") (pinfunction "GND_49") (pintype "power_in"))
      (node (ref "IC5") (pin "74") (pinfunction "GND_74") (pintype "power_in"))
      (node (ref "IC5") (pin "94") (pinfunction "BOOT0_94") (pintype "input"))
      (node (ref "IC5") (pin "99") (pinfunction "GND_99") (pintype "power_in"))
      (node (ref "IC6") (pin "1") (pinfunction "GND_1") (pintype "power_in"))
      (node (ref "IC7") (pin "15") (pinfunction "AGND_15") (pintype "bidirectional"))
      (node (ref "IC7") (pin "19") (pinfunction "AGND_19") (pintype "bidirectional"))
      (node (ref "IC7") (pin "35") (pinfunction "IOGND_35") (pintype "bidirectional"))
      (node (ref "IC7") (pin "36") (pinfunction "DGND_36") (pintype "bidirectional"))
      (node (ref "IC7") (pin "47") (pinfunction "IOGND_47") (pintype "bidirectional"))
      (node (ref "IC8") (pin "1") (pinfunction "GND_1") (pintype "bidirectional"))
      (node (ref "IC8") (pin "10") (pinfunction "GND_10") (pintype "bidirectional"))
      (node (ref "IC8") (pin "12") (pinfunction "GND_12") (pintype "bidirectional"))
      (node (ref "IC8") (pin "13") (pinfunction "GND_13") (pintype "bidirectional"))
      (node (ref "IC8") (pin "18") (pinfunction "GND_18") (pintype "bidirectional"))
      (node (ref "IC8") (pin "20") (pinfunction "GND_20") (pintype "bidirectional"))
      (node (ref "IC8") (pin "22") (pinfunction "GND_22") (pintype "bidirectional"))
      (node (ref "IC8") (pin "5") (pinfunction "GND_5") (pintype "bidirectional"))
      (node (ref "IC8") (pin "7") (pinfunction "GND_7") (pintype "bidirectional"))
      (node (ref "IC8") (pin "9") (pinfunction "GND_9") (pintype "bidirectional"))
      (node (ref "IC8") (pin "PAD1") (pinfunction "GND_PAD1") (pintype "bidirectional"))
      (node (ref "IC8") (pin "PAD2") (pinfunction "GND_PAD2") (pintype "bidirectional"))
      (node (ref "IC9") (pin "13") (pinfunction "GND_13") (pintype "bidirectional"))
      (node (ref "IC9") (pin "20") (pinfunction "GND_20") (pintype "bidirectional"))
      (node (ref "IC9") (pin "21") (pinfunction "GND_21") (pintype "bidirectional"))
      (node (ref "IC9") (pin "23") (pinfunction "GND_23") (pintype "bidirectional"))
      (node (ref "IC9") (pin "24") (pinfunction "GND_24") (pintype "bidirectional"))
      (node (ref "IC9") (pin "5") (pinfunction "GND_5") (pintype "bidirectional"))
      (node (ref "IC9") (pin "PAD") (pinfunction "GND_PAD") (pintype "bidirectional"))
      (node (ref "LED3") (pin "C") (pinfunction "C_C") (pintype "passive"))
      (node (ref "PWR") (pin "C") (pinfunction "C_C") (pintype "passive"))
      (node (ref "Q1") (pin "2") (pinfunction "2_2") (pintype "passive"))
      (node (ref "Q3") (pin "2") (pinfunction "GND_2") (pintype "power_in"))
      (node (ref "Q4") (pin "2") (pinfunction "GND1_2") (pintype "bidirectional"))
      (node (ref "Q4") (pin "4") (pinfunction "GND2_4") (pintype "bidirectional"))
      (node (ref "R17") (pin "1") (pinfunction "1_1") (pintype "passive"))
      (node (ref "RESET1") (pin "1") (pinfunction "1_1") (pintype "bidirectional"))
      (node (ref "RESET1") (pin "2") (pinfunction "2_2") (pintype "bidirectional"))
      (node (ref "RN1") (pin "6") (pinfunction "2_6") (pintype "passive"))
      (node (ref "USB1") (pin "5") (pinfunction "GND_5") (pintype "bidirectional"))
      (node (ref "X1") (pin "GND") (pinfunction "GND_GND") (pintype "bidirectional"))
      (node (ref "X2") (pin "GND1") (pinfunction "GND_GND1") (pintype "power_in"))
      (node (ref "X2") (pin "GND2") (pinfunction "GND1_GND2") (pintype "power_in"))
      (node (ref "X2") (pin "GND3") (pinfunction "GND2_GND3") (pintype "power_in"))
      (node (ref "X2") (pin "GND4") (pinfunction "GND3_GND4") (pintype "power_in"))
      (node (ref "X3") (pin "GND1") (pinfunction "GND_GND1") (pintype "power_in"))
      (node (ref "X3") (pin "GND2") (pinfunction "GND1_GND2") (pintype "power_in"))
      (node (ref "X3") (pin "GND3") (pinfunction "GND2_GND3") (pintype "power_in"))
      (node (ref "X3") (pin "GND4") (pinfunction "GND3_GND4") (pintype "power_in"))
    )
    (net (code "29") (name "JTAG_UNUSED1") (class "Default")
      (node (ref "IC5") (pin "77") (pinfunction "P15_77") (pintype "bidirectional"))
    )
    (net (code "30") (name "JTAG_UNUSED2") (class "Default")
      (node (ref "IC5") (pin "89") (pinfunction "P3_89") (pintype "bidirectional"))
    )
    (net (code "31") (name "JTD-A2M1") (class "Default")
      (node (ref "IC1") (pin "2") (pinfunction "I_2") (pintype "input"))
      (node (ref "IC2") (pin "23") (pinfunction "ADBUS1_23") (pintype "bidirectional"))
      (node (ref "RN1") (pin "2") (pinfunction "1_2") (pintype "passive"))
    )
    (net (code "32") (name "JTD-M2A1") (class "Default")
      (node (ref "IC2") (pin "22") (pinfunction "ADBUS2_22") (pintype "bidirectional"))
      (node (ref "RN2") (pin "4") (pinfunction "1_4") (pintype "passive"))
    )
    (net (code "33") (name "LCD_ON") (class "Default")
      (node (ref "IC5") (pin "69") (pinfunction "P10_69") (pintype "bidirectional"))
      (node (ref "IC6") (pin "19") (pinfunction "LCD_ON_19") (pintype "bidirectional"))
    )
    (net (code "34") (name "LCD_RESET") (class "Default")
      (node (ref "IC5") (pin "68") (pinfunction "P9_68") (pintype "bidirectional"))
      (node (ref "IC6") (pin "17") (pinfunction "RESET_17") (pintype "bidirectional"))
    )
    (net (code "35") (name "LED0") (class "Default")
      (node (ref "IC5") (pin "28") (pinfunction "P4_28") (pintype "bidirectional"))
      (node (ref "LED2") (pin "C") (pinfunction "C_C") (pintype "passive"))
    )
    (net (code "36") (name "LED1") (class "Default")
      (node (ref "IC5") (pin "29") (pinfunction "P5_29") (pintype "bidirectional"))
      (node (ref "LED1") (pin "C") (pinfunction "C_C") (pintype "passive"))
    )
    (net (code "37") (name "MII_COL") (class "Default")
      (node (ref "IC5") (pin "25") (pinfunction "P3_25") (pintype "bidirectional"))
      (node (ref "RN8") (pin "2") (pinfunction "1_2") (pintype "passive"))
    )
    (net (code "38") (name "MII_CRS") (class "Default")
      (node (ref "IC5") (pin "22") (pinfunction "P0_22") (pintype "bidirectional"))
      (node (ref "RN9") (pin "4") (pinfunction "1_4") (pintype "passive"))
    )
    (net (code "39") (name "MII_INT") (class "Default")
      (node (ref "IC5") (pin "4") (pinfunction "P5_4") (pintype "bidirectional"))
      (node (ref "IC7") (pin "7") (pinfunction "PWR_DOWN/INT_7") (pintype "bidirectional"))
    )
    (net (code "40") (name "MII_MDC") (class "Default")
      (node (ref "IC5") (pin "16") (pinfunction "P1_16") (pintype "bidirectional"))
      (node (ref "IC7") (pin "31") (pinfunction "MDC_31") (pintype "bidirectional"))
    )
    (net (code "41") (name "MII_MDIO") (class "Default")
      (node (ref "IC5") (pin "24") (pinfunction "P2_24") (pintype "bidirectional"))
      (node (ref "IC7") (pin "30") (pinfunction "MDIO_30") (pintype "bidirectional"))
      (node (ref "R14") (pin "1") (pinfunction "1_1") (pintype "passive"))
    )
    (net (code "42") (name "MII_RXD0") (class "Default")
      (node (ref "IC5") (pin "32") (pinfunction "P4_32") (pintype "bidirectional"))
      (node (ref "RN8") (pin "3") (pinfunction "1_3") (pintype "passive"))
    )
    (net (code "43") (name "MII_RXD1") (class "Default")
      (node (ref "IC5") (pin "33") (pinfunction "P5_33") (pintype "bidirectional"))
      (node (ref "RN8") (pin "4") (pinfunction "1_4") (pintype "passive"))
    )
    (net (code "44") (name "MII_RXD2") (class "Default")
      (node (ref "IC5") (pin "34") (pinfunction "P0_34") (pintype "bidirectional"))
      (node (ref "RN6") (pin "1") (pinfunction "1_1") (pintype "passive"))
    )
    (net (code "45") (name "MII_RXD3") (class "Default")
      (node (ref "IC5") (pin "35") (pinfunction "P1_35") (pintype "bidirectional"))
      (node (ref "RN6") (pin "2") (pinfunction "1_2") (pintype "passive"))
    )
    (net (code "46") (name "MII_RX_CLK") (class "Default")
      (node (ref "IC5") (pin "23") (pinfunction "P1_23") (pintype "bidirectional"))
      (node (ref "RN9") (pin "2") (pinfunction "1_2") (pintype "passive"))
    )
    (net (code "47") (name "MII_RX_DV") (class "Default")
      (node (ref "IC5") (pin "31") (pinfunction "P7_31") (pintype "bidirectional"))
      (node (ref "RN9") (pin "3") (pinfunction "1_3") (pintype "passive"))
    )
    (net (code "48") (name "MII_RX_ER") (class "Default")
      (node (ref "IC5") (pin "46") (pinfunction "P10_46") (pintype "bidirectional"))
      (node (ref "RN8") (pin "1") (pinfunction "1_1") (pintype "passive"))
    )
    (net (code "49") (name "MII_TXD0") (class "Default")
      (node (ref "IC5") (pin "51") (pinfunction "P12_51") (pintype "bidirectional"))
      (node (ref "RN4") (pin "1") (pinfunction "1_1") (pintype "passive"))
    )
    (net (code "50") (name "MII_TXD1") (class "Default")
      (node (ref "IC5") (pin "52") (pinfunction "P13_52") (pintype "bidirectional"))
      (node (ref "RN4") (pin "2") (pinfunction "1_2") (pintype "passive"))
    )
    (net (code "51") (name "MII_TXD2") (class "Default")
      (node (ref "IC5") (pin "17") (pinfunction "P2_17") (pintype "bidirectional"))
      (node (ref "RN4") (pin "3") (pinfunction "1_3") (pintype "passive"))
    )
    (net (code "52") (name "MII_TXD3") (class "Default")
      (node (ref "IC5") (pin "95") (pinfunction "P8_95") (pintype "bidirectional"))
      (node (ref "RN4") (pin "4") (pinfunction "1_4") (pintype "passive"))
    )
    (net (code "53") (name "MII_TX_CLK") (class "Default")
      (node (ref "IC5") (pin "18") (pinfunction "P3_18") (pintype "bidirectional"))
      (node (ref "RN6") (pin "3") (pinfunction "1_3") (pintype "passive"))
    )
    (net (code "54") (name "MII_TX_EN") (class "Default")
      (node (ref "IC5") (pin "47") (pinfunction "P11_47") (pintype "bidirectional"))
      (node (ref "RN6") (pin "4") (pinfunction "1_4") (pintype "passive"))
    )
    (net (code "55") (name "Net-(100MBIT-PadA)") (class "Default")
      (node (ref "100MBIT") (pin "A") (pinfunction "A_A") (pintype "passive"))
      (node (ref "R11") (pin "1") (pinfunction "1_1") (pintype "passive"))
    )
    (net (code "56") (name "Net-(C17-Pad1)") (class "Default")
      (node (ref "C17") (pin "1") (pinfunction "1_1") (pintype "passive"))
      (node (ref "IC5") (pin "48") (pinfunction "VCAP_48") (pintype "power_in"))
    )
    (net (code "57") (name "Net-(C18-Pad1)") (class "Default")
      (node (ref "C18") (pin "1") (pinfunction "1_1") (pintype "passive"))
      (node (ref "IC5") (pin "73") (pinfunction "VCAP_73") (pintype "power_in"))
    )
    (net (code "58") (name "Net-(C33-Pad1)") (class "Default")
      (node (ref "C33") (pin "1") (pinfunction "1_1") (pintype "passive"))
      (node (ref "C41") (pin "1") (pinfunction "1_1") (pintype "passive"))
      (node (ref "R18") (pin "2") (pinfunction "2_2") (pintype "passive"))
      (node (ref "R19") (pin "1") (pinfunction "1_1") (pintype "passive"))
    )
    (net (code "59") (name "Net-(C33-Pad2)") (class "Default")
      (node (ref "C33") (pin "2") (pinfunction "2_2") (pintype "passive"))
      (node (ref "C38") (pin "2") (pinfunction "2_2") (pintype "passive"))
      (node (ref "C42") (pin "1") (pinfunction "1_1") (pintype "passive"))
      (node (ref "R19") (pin "2") (pinfunction "2_2") (pintype "passive"))
    )
    (net (code "60") (name "Net-(C39-Pad2)") (class "Default")
      (node (ref "C39") (pin "2") (pinfunction "2_2") (pintype "passive"))
      (node (ref "C43") (pin "1") (pinfunction "1_1") (pintype "passive"))
      (node (ref "R20") (pin "1") (pinfunction "1_1") (pintype "passive"))
    )
    (net (code "61") (name "Net-(C47-Pad2)") (class "Default")
      (node (ref "C47") (pin "2") (pinfunction "2_2") (pintype "passive"))
      (node (ref "C48") (pin "1") (pinfunction "1_1") (pintype "passive"))
      (node (ref "R21") (pin "1") (pinfunction "1_1") (pintype "passive"))
    )
    (net (code "62") (name "Net-(ETH-LED_GR+)") (class "Default")
      (node (ref "ETH") (pin "13") (pinfunction "LED_GR+_13") (pintype "bidirectional"))
      (node (ref "R12") (pin "1") (pinfunction "1_1") (pintype "passive"))
    )
    (net (code "63") (name "Net-(ETH-LED_GR-)") (class "Default")
      (node (ref "ETH") (pin "14") (pinfunction "LED_GR-_14") (pintype "bidirectional"))
      (node (ref "IC7") (pin "28") (pinfunction "LED_LINK_28") (pintype "bidirectional"))
      (node (ref "RN7") (pin "1") (pinfunction "1_1") (pintype "passive"))
    )
    (net (code "64") (name "Net-(ETH-LED_YE+)") (class "Default")
      (node (ref "ETH") (pin "11") (pinfunction "LED_YE+_11") (pintype "bidirectional"))
      (node (ref "R13") (pin "1") (pinfunction "1_1") (pintype "passive"))
    )
    (net (code "65") (name "Net-(ETH-LED_YE-)") (class "Default")
      (node (ref "ETH") (pin "12") (pinfunction "LED_YE-_12") (pintype "bidirectional"))
      (node (ref "IC7") (pin "26") (pinfunction "LED_ACT/COL_26") (pintype "bidirectional"))
      (node (ref "RN7") (pin "3") (pinfunction "1_3") (pintype "passive"))
    )
    (net (code "66") (name "Net-(ETH-RD+)") (class "Default")
      (node (ref "ETH") (pin "4") (pinfunction "RD+_4") (pintype "bidirectional"))
      (node (ref "IC7") (pin "14") (pinfunction "RD+_14") (pintype "bidirectional"))
      (node (ref "RN5") (pin "3") (pinfunction "1_3") (pintype "passive"))
    )
    (net (code "67") (name "Net-(ETH-RD-)") (class "Default")
      (node (ref "ETH") (pin "6") (pinfunction "RD-_6") (pintype "bidirectional"))
      (node (ref "IC7") (pin "13") (pinfunction "RD-_13") (pintype "bidirectional"))
      (node (ref "RN5") (pin "4") (pinfunction "1_4") (pintype "passive"))
    )
    (net (code "68") (name "Net-(ETH-TD+)") (class "Default")
      (node (ref "ETH") (pin "1") (pinfunction "TD+_1") (pintype "bidirectional"))
      (node (ref "IC7") (pin "17") (pinfunction "TD+_17") (pintype "bidirectional"))
      (node (ref "RN5") (pin "1") (pinfunction "1_1") (pintype "passive"))
    )
    (net (code "69") (name "Net-(ETH-TD-)") (class "Default")
      (node (ref "ETH") (pin "3") (pinfunction "TD-_3") (pintype "bidirectional"))
      (node (ref "IC7") (pin "16") (pinfunction "TD-_16") (pintype "bidirectional"))
      (node (ref "RN5") (pin "2") (pinfunction "1_2") (pintype "passive"))
    )
    (net (code "70") (name "Net-(IC1A-O)") (class "Default")
      (node (ref "IC1") (pin "4") (pinfunction "O_4") (pintype "tri_state"))
      (node (ref "RN2") (pin "1") (pinfunction "1_1") (pintype "passive"))
    )
    (net (code "71") (name "Net-(IC2-3V3OUT)") (class "Default")
      (node (ref "C2") (pin "1") (pinfunction "1_1") (pintype "passive"))
      (node (ref "IC2") (pin "6") (pinfunction "3V3OUT_6") (pintype "bidirectional"))
    )
    (net (code "72") (name "Net-(IC2-AVCC)") (class "Default")
      (node (ref "C1") (pin "1") (pinfunction "1_1") (pintype "passive"))
      (node (ref "IC2") (pin "46") (pinfunction "AVCC_46") (pintype "bidirectional"))
      (node (ref "R1") (pin "1") (pinfunction "1_1") (pintype "passive"))
    )
    (net (code "73") (name "Net-(IC2-BDBUS0)") (class "Default")
      (node (ref "IC2") (pin "40") (pinfunction "BDBUS0_40") (pintype "bidirectional"))
      (node (ref "RN3") (pin "4") (pinfunction "1_4") (pintype "passive"))
    )
    (net (code "74") (name "Net-(IC2-BDBUS1)") (class "Default")
      (node (ref "IC2") (pin "39") (pinfunction "BDBUS1_39") (pintype "bidirectional"))
      (node (ref "RN3") (pin "1") (pinfunction "1_1") (pintype "passive"))
    )
    (net (code "75") (name "Net-(IC2-EECS)") (class "Default")
      (node (ref "IC2") (pin "48") (pinfunction "EECS_48") (pintype "bidirectional"))
      (node (ref "IC4") (pin "5") (pinfunction "CS_5") (pintype "input"))
    )
    (net (code "76") (name "Net-(IC2-EEDATA)") (class "Default")
      (node (ref "IC2") (pin "2") (pinfunction "EEDATA_2") (pintype "bidirectional"))
      (node (ref "IC4") (pin "3") (pinfunction "DI_3") (pintype "input"))
      (node (ref "R7") (pin "2") (pinfunction "2_2") (pintype "passive"))
    )
    (net (code "77") (name "Net-(IC2-EESK)") (class "Default")
      (node (ref "IC2") (pin "1") (pinfunction "EESK_1") (pintype "bidirectional"))
      (node (ref "IC4") (pin "4") (pinfunction "CLK_4") (pintype "input"))
    )
    (net (code "78") (name "Net-(IC2-RSTOUT)") (class "Default")
      (node (ref "IC2") (pin "5") (pinfunction "RSTOUT_5") (pintype "bidirectional"))
      (node (ref "R4") (pin "1") (pinfunction "1_1") (pintype "passive"))
    )
    (net (code "79") (name "Net-(IC2-USBDM)") (class "Default")
      (node (ref "IC2") (pin "8") (pinfunction "USBDM_8") (pintype "bidirectional"))
      (node (ref "R2") (pin "2") (pinfunction "2_2") (pintype "passive"))
    )
    (net (code "80") (name "Net-(IC2-USBDP)") (class "Default")
      (node (ref "IC2") (pin "7") (pinfunction "USBDP_7") (pintype "bidirectional"))
      (node (ref "R3") (pin "2") (pinfunction "2_2") (pintype "passive"))
      (node (ref "R4") (pin "2") (pinfunction "2_2") (pintype "passive"))
    )
    (net (code "81") (name "Net-(IC2-XTIN)") (class "Default")
      (node (ref "IC2") (pin "43") (pinfunction "XTIN_43") (pintype "bidirectional"))
      (node (ref "Q1") (pin "1") (pinfunction "1_1") (pintype "passive"))
      (node (ref "R5") (pin "2") (pinfunction "2_2") (pintype "passive"))
    )
    (net (code "82") (name "Net-(IC2-XTOUT)") (class "Default")
      (node (ref "IC2") (pin "44") (pinfunction "XTOUT_44") (pintype "bidirectional"))
      (node (ref "Q1") (pin "3") (pinfunction "3_3") (pintype "passive"))
      (node (ref "R5") (pin "1") (pinfunction "1_1") (pintype "passive"))
    )
    (net (code "83") (name "Net-(IC3-SW)") (class "Default")
      (node (ref "IC3") (pin "5") (pinfunction "SW_5") (pintype "bidirectional"))
      (node (ref "L2") (pin "P$2") (pinfunction "2_P$2") (pintype "passive"))
    )
    (net (code "84") (name "Net-(IC4-DO)") (class "Default")
      (node (ref "IC4") (pin "1") (pinfunction "DO_1") (pintype "tri_state"))
      (node (ref "R7") (pin "1") (pinfunction "1_1") (pintype "passive"))
      (node (ref "R8") (pin "1") (pinfunction "1_1") (pintype "passive"))
    )
    (net (code "85") (name "Net-(IC5D-P14)") (class "Default")
      (node (ref "C12") (pin "1") (pinfunction "1_1") (pintype "passive"))
      (node (ref "IC5") (pin "8") (pinfunction "P14_8") (pintype "bidirectional"))
      (node (ref "Q2") (pin "1") (pinfunction "1_1") (pintype "passive"))
    )
    (net (code "86") (name "Net-(IC5D-P15)") (class "Default")
      (node (ref "C13") (pin "1") (pinfunction "1_1") (pintype "passive"))
      (node (ref "IC5") (pin "9") (pinfunction "P15_9") (pintype "bidirectional"))
      (node (ref "Q2") (pin "2") (pinfunction "2_2") (pintype "passive"))
    )
    (net (code "87") (name "Net-(IC5I-VBAT)") (class "Default")
      (node (ref "IC5") (pin "6") (pinfunction "VBAT_6") (pintype "passive"))
      (node (ref "X1") (pin "POS1") (pinfunction "POS1_POS1") (pintype "bidirectional"))
      (node (ref "X1") (pin "POS2") (pinfunction "POS2_POS2") (pintype "bidirectional"))
    )
    (net (code "88") (name "Net-(IC6-VCC3.3)") (class "Default")
      (node (ref "C15") (pin "1") (pinfunction "1_1") (pintype "passive"))
      (node (ref "IC6") (pin "2") (pinfunction "VCC3.3_2") (pintype "power_in"))
      (node (ref "L3") (pin "1") (pinfunction "1_1") (pintype "passive"))
    )
    (net (code "89") (name "Net-(IC7-COL)") (class "Default")
      (node (ref "IC7") (pin "42") (pinfunction "COL_42") (pintype "bidirectional"))
      (node (ref "RN8") (pin "7") (pinfunction "2_7") (pintype "passive"))
    )
    (net (code "90") (name "Net-(IC7-CRS{slash}CRS_DV)") (class "Default")
      (node (ref "IC7") (pin "40") (pinfunction "CRS/CRS_DV_40") (pintype "bidirectional"))
      (node (ref "RN9") (pin "5") (pinfunction "2_5") (pintype "passive"))
    )
    (net (code "91") (name "Net-(IC7-LED_SPEED)") (class "Default")
      (node (ref "100MBIT") (pin "C") (pinfunction "C_C") (pintype "passive"))
      (node (ref "IC7") (pin "27") (pinfunction "LED_SPEED_27") (pintype "bidirectional"))
      (node (ref "RN7") (pin "2") (pinfunction "1_2") (pintype "passive"))
    )
    (net (code "92") (name "Net-(IC7-PFBIN1)") (class "Default")
      (node (ref "C29") (pin "1") (pinfunction "1_1") (pintype "passive"))
      (node (ref "C30") (pin "1") (pinfunction "1_1") (pintype "passive"))
      (node (ref "C31") (pin "1") (pinfunction "1_1") (pintype "passive"))
      (node (ref "C32") (pin "1") (pinfunction "1_1") (pintype "passive"))
      (node (ref "IC7") (pin "18") (pinfunction "PFBIN1_18") (pintype "bidirectional"))
      (node (ref "IC7") (pin "23") (pinfunction "PFBOUT_23") (pintype "bidirectional"))
      (node (ref "IC7") (pin "37") (pinfunction "PFBIN2_37") (pintype "bidirectional"))
    )
    (net (code "93") (name "Net-(IC7-RBIAS)") (class "Default")
      (node (ref "IC7") (pin "24") (pinfunction "RBIAS_24") (pintype "bidirectional"))
      (node (ref "R17") (pin "2") (pinfunction "2_2") (pintype "passive"))
    )
    (net (code "94") (name "Net-(IC7-RESV-Pad20)") (class "Default")
      (node (ref "IC7") (pin "20") (pinfunction "RESV_20") (pintype "bidirectional"))
      (node (ref "R15") (pin "1") (pinfunction "1_1") (pintype "passive"))
    )
    (net (code "95") (name "Net-(IC7-RESV-Pad21)") (class "Default")
      (node (ref "IC7") (pin "21") (pinfunction "RESV_21") (pintype "bidirectional"))
      (node (ref "R16") (pin "1") (pinfunction "1_1") (pintype "passive"))
    )
    (net (code "96") (name "Net-(IC7-RXD_0)") (class "Default")
      (node (ref "IC7") (pin "43") (pinfunction "RXD_0_43") (pintype "bidirectional"))
      (node (ref "RN8") (pin "6") (pinfunction "2_6") (pintype "passive"))
    )
    (net (code "97") (name "Net-(IC7-RXD_1)") (class "Default")
      (node (ref "IC7") (pin "44") (pinfunction "RXD_1_44") (pintype "bidirectional"))
      (node (ref "RN8") (pin "5") (pinfunction "2_5") (pintype "passive"))
    )
    (net (code "98") (name "Net-(IC7-RXD_2)") (class "Default")
      (node (ref "IC7") (pin "45") (pinfunction "RXD_2_45") (pintype "bidirectional"))
      (node (ref "RN6") (pin "8") (pinfunction "2_8") (pintype "passive"))
    )
    (net (code "99") (name "Net-(IC7-RXD_3)") (class "Default")
      (node (ref "IC7") (pin "46") (pinfunction "RXD_3_46") (pintype "bidirectional"))
      (node (ref "RN6") (pin "7") (pinfunction "2_7") (pintype "passive"))
    )
    (net (code "100") (name "Net-(IC7-RX_CLK)") (class "Default")
      (node (ref "IC7") (pin "38") (pinfunction "RX_CLK_38") (pintype "bidirectional"))
      (node (ref "RN9") (pin "7") (pinfunction "2_7") (pintype "passive"))
    )
    (net (code "101") (name "Net-(IC7-RX_DV)") (class "Default")
      (node (ref "IC7") (pin "39") (pinfunction "RX_DV_39") (pintype "bidirectional"))
      (node (ref "RN9") (pin "6") (pinfunction "2_6") (pintype "passive"))
    )
    (net (code "102") (name "Net-(IC7-RX_ER)") (class "Default")
      (node (ref "IC7") (pin "41") (pinfunction "RX_ER_41") (pintype "bidirectional"))
      (node (ref "RN8") (pin "8") (pinfunction "2_8") (pintype "passive"))
    )
    (net (code "103") (name "Net-(IC7-TXD_0)") (class "Default")
      (node (ref "IC7") (pin "3") (pinfunction "TXD_0_3") (pintype "bidirectional"))
      (node (ref "RN4") (pin "8") (pinfunction "2_8") (pintype "passive"))
    )
    (net (code "104") (name "Net-(IC7-TXD_1)") (class "Default")
      (node (ref "IC7") (pin "4") (pinfunction "TXD_1_4") (pintype "bidirectional"))
      (node (ref "RN4") (pin "7") (pinfunction "2_7") (pintype "passive"))
    )
    (net (code "105") (name "Net-(IC7-TXD_2)") (class "Default")
      (node (ref "IC7") (pin "5") (pinfunction "TXD_2_5") (pintype "bidirectional"))
      (node (ref "RN4") (pin "6") (pinfunction "2_6") (pintype "passive"))
    )
    (net (code "106") (name "Net-(IC7-TXD_3)") (class "Default")
      (node (ref "IC7") (pin "6") (pinfunction "TXD_3_6") (pintype "bidirectional"))
      (node (ref "RN4") (pin "5") (pinfunction "2_5") (pintype "passive"))
    )
    (net (code "107") (name "Net-(IC7-TX_CLK)") (class "Default")
      (node (ref "IC7") (pin "1") (pinfunction "TX_CLK_1") (pintype "bidirectional"))
      (node (ref "RN6") (pin "6") (pinfunction "2_6") (pintype "passive"))
    )
    (net (code "108") (name "Net-(IC7-TX_EN)") (class "Default")
      (node (ref "IC7") (pin "2") (pinfunction "TX_EN_2") (pintype "bidirectional"))
      (node (ref "RN6") (pin "5") (pinfunction "2_5") (pintype "passive"))
    )
    (net (code "109") (name "Net-(IC7-X1)") (class "Default")
      (node (ref "IC7") (pin "34") (pinfunction "X1_34") (pintype "bidirectional"))
      (node (ref "Q3") (pin "3") (pinfunction "FO_3") (pintype "output"))
    )
    (net (code "110") (name "Net-(IC8-ANT1)") (class "Default")
      (node (ref "C39") (pin "1") (pinfunction "1_1") (pintype "passive"))
      (node (ref "IC8") (pin "8") (pinfunction "ANT1_8") (pintype "bidirectional"))
    )
    (net (code "111") (name "Net-(IC8-ANT2)") (class "Default")
      (node (ref "C47") (pin "1") (pinfunction "1_1") (pintype "passive"))
      (node (ref "IC8") (pin "6") (pinfunction "ANT2_6") (pintype "bidirectional"))
    )
    (net (code "112") (name "Net-(IC8-CHL)") (class "Default")
      (node (ref "C50") (pin "1") (pinfunction "1_1") (pintype "passive"))
      (node (ref "C51") (pin "1") (pinfunction "1_1") (pintype "passive"))
      (node (ref "C52") (pin "1") (pinfunction "1_1") (pintype "passive"))
      (node (ref "C53") (pin "1") (pinfunction "1_1") (pintype "passive"))
      (node (ref "C54") (pin "1") (pinfunction "1_1") (pintype "passive"))
      (node (ref "C55") (pin "1") (pinfunction "1_1") (pintype "passive"))
      (node (ref "IC8") (pin "11") (pinfunction "VDD_11") (pintype "bidirectional"))
      (node (ref "IC8") (pin "14") (pinfunction "VCC2_14") (pintype "bidirectional"))
      (node (ref "IC8") (pin "16") (pinfunction "VCC1_16") (pintype "bidirectional"))
      (node (ref "IC8") (pin "19") (pinfunction "CHL_19") (pintype "bidirectional"))
      (node (ref "IC8") (pin "3") (pinfunction "CSD_3") (pintype "bidirectional"))
      (node (ref "L5") (pin "2") (pinfunction "2_2") (pintype "passive"))
    )
    (net (code "113") (name "Net-(IC8-RFIN)") (class "Default")
      (node (ref "C38") (pin "1") (pinfunction "1_1") (pintype "passive"))
      (node (ref "IC8") (pin "21") (pinfunction "RFIN_21") (pintype "bidirectional"))
    )
    (net (code "114") (name "Net-(IC9-BUSY)") (class "Default")
      (node (ref "IC9") (pin "7") (pinfunction "BUSY_7") (pintype "bidirectional"))
      (node (ref "RN11") (pin "8") (pinfunction "2_8") (pintype "passive"))
    )
    (net (code "115") (name "Net-(IC9-DCC_FB)") (class "Default")
      (node (ref "C45") (pin "1") (pinfunction "1_1") (pintype "passive"))
      (node (ref "C46") (pin "1") (pinfunction "1_1") (pintype "passive"))
      (node (ref "IC9") (pin "12") (pinfunction "DCC_FB_12") (pintype "bidirectional"))
      (node (ref "IC9") (pin "2") (pinfunction "VDD_IN_2") (pintype "bidirectional"))
    )
    (net (code "116") (name "Net-(IC9-DIO1)") (class "Default")
      (node (ref "IC9") (pin "8") (pinfunction "DIO1_8") (pintype "bidirectional"))
      (node (ref "RN11") (pin "5") (pinfunction "2_5") (pintype "passive"))
    )
    (net (code "117") (name "Net-(IC9-MISO)") (class "Default")
      (node (ref "IC9") (pin "16") (pinfunction "MISO_16") (pintype "bidirectional"))
      (node (ref "RN10") (pin "5") (pinfunction "2_5") (pintype "passive"))
    )
    (net (code "118") (name "Net-(IC9-MOSI)") (class "Default")
      (node (ref "IC9") (pin "17") (pinfunction "MOSI_17") (pintype "bidirectional"))
      (node (ref "RN10") (pin "6") (pinfunction "2_6") (pintype "passive"))
    )
    (net (code "119") (name "Net-(IC9-RFIO)") (class "Default")
      (node (ref "C40") (pin "1") (pinfunction "1_1") (pintype "passive"))
      (node (ref "IC9") (pin "22") (pinfunction "RFIO_22") (pintype "bidirectional"))
      (node (ref "R18") (pin "1") (pinfunction "1_1") (pintype "passive"))
    )
    (net (code "120") (name "Net-(IC9-SCK)") (class "Default")
      (node (ref "IC9") (pin "18") (pinfunction "SCK_18") (pintype "bidirectional"))
      (node (ref "RN10") (pin "7") (pinfunction "2_7") (pintype "passive"))
    )
    (net (code "121") (name "Net-(IC9-VBAT)") (class "Default")
      (node (ref "C34") (pin "1") (pinfunction "1_1") (pintype "passive"))
      (node (ref "C35") (pin "1") (pinfunction "1_1") (pintype "passive"))
      (node (ref "C36") (pin "1") (pinfunction "1_1") (pintype "passive"))
      (node (ref "C37") (pin "1") (pinfunction "1_1") (pintype "passive"))
      (node (ref "IC9") (pin "11") (pinfunction "V_DIO_11") (pintype "bidirectional"))
      (node (ref "IC9") (pin "15") (pinfunction "VBAT_15") (pintype "bidirectional"))
      (node (ref "IC9") (pin "3") (pinfunction "~{RESET}_3") (pintype "bidirectional"))
      (node (ref "L4") (pin "2") (pinfunction "2_2") (pintype "passive"))
    )
    (net (code "122") (name "Net-(IC9-VR_PA)") (class "Default")
      (node (ref "C56") (pin "1") (pinfunction "1_1") (pintype "passive"))
      (node (ref "IC9") (pin "1") (pinfunction "VR_PA_1") (pintype "bidirectional"))
    )
    (net (code "123") (name "Net-(IC9-XTA)") (class "Default")
      (node (ref "IC9") (pin "6") (pinfunction "XTA_6") (pintype "bidirectional"))
      (node (ref "Q4") (pin "1") (pinfunction "1_1") (pintype "passive"))
    )
    (net (code "124") (name "Net-(IC9-XTB)") (class "Default")
      (node (ref "IC9") (pin "4") (pinfunction "XTB_4") (pintype "bidirectional"))
      (node (ref "Q4") (pin "3") (pinfunction "2_3") (pintype "passive"))
    )
    (net (code "125") (name "Net-(IC9-~{CS})") (class "Default")
      (node (ref "IC9") (pin "19") (pinfunction "~{CS}_19") (pintype "bidirectional"))
      (node (ref "RN10") (pin "8") (pinfunction "2_8") (pintype "passive"))
    )
    (net (code "126") (name "Net-(LED1-PadA)") (class "Default")
      (node (ref "LED1") (pin "A") (pinfunction "A_A") (pintype "passive"))
      (node (ref "R9") (pin "1") (pinfunction "1_1") (pintype "passive"))
    )
    (net (code "127") (name "Net-(LED2-PadA)") (class "Default")
      (node (ref "LED2") (pin "A") (pinfunction "A_A") (pintype "passive"))
      (node (ref "R10") (pin "1") (pinfunction "1_1") (pintype "passive"))
    )
    (net (code "128") (name "Net-(LED3-PadA)") (class "Default")
      (node (ref "LED3") (pin "A") (pinfunction "A_A") (pintype "passive"))
      (node (ref "R22") (pin "1") (pinfunction "1_1") (pintype "passive"))
    )
    (net (code "129") (name "Net-(PWR-PadA)") (class "Default")
      (node (ref "PWR") (pin "A") (pinfunction "A_A") (pintype "passive"))
      (node (ref "R6") (pin "1") (pinfunction "1_1") (pintype "passive"))
    )
    (net (code "130") (name "Net-(USB1-D+)") (class "Default")
      (node (ref "R3") (pin "1") (pinfunction "1_1") (pintype "passive"))
      (node (ref "USB1") (pin "3") (pinfunction "D+_3") (pintype "bidirectional"))
    )
    (net (code "131") (name "Net-(USB1-D-)") (class "Default")
      (node (ref "R2") (pin "1") (pinfunction "1_1") (pintype "passive"))
      (node (ref "USB1") (pin "2") (pinfunction "D-_2") (pintype "bidirectional"))
    )
    (net (code "132") (name "Net-(USB1-VCC)") (class "Default")
      (node (ref "C8") (pin "1") (pinfunction "1_1") (pintype "passive"))
      (node (ref "L1") (pin "1") (pinfunction "1_1") (pintype "passive"))
      (node (ref "USB1") (pin "1") (pinfunction "VCC_1") (pintype "bidirectional"))
    )
    (net (code "133") (name "Net-(X2-1)") (class "Default")
      (node (ref "C44") (pin "1") (pinfunction "1_1") (pintype "passive"))
      (node (ref "R20") (pin "2") (pinfunction "2_2") (pintype "passive"))
      (node (ref "X2") (pin "C") (pinfunction "1_C") (pintype "passive"))
    )
    (net (code "134") (name "Net-(X3-1)") (class "Default")
      (node (ref "C49") (pin "1") (pinfunction "1_1") (pintype "passive"))
      (node (ref "R21") (pin "2") (pinfunction "2_2") (pintype "passive"))
      (node (ref "X3") (pin "C") (pinfunction "1_C") (pintype "passive"))
    )
    (net (code "135") (name "PHY_RESET") (class "Default")
      (node (ref "IC5") (pin "30") (pinfunction "P6_30") (pintype "bidirectional"))
      (node (ref "IC7") (pin "29") (pinfunction "RESET_N_29") (pintype "bidirectional"))
    )
    (net (code "136") (name "SPI2_MISO") (class "Default")
      (node (ref "IC5") (pin "53") (pinfunction "P14_53") (pintype "bidirectional"))
      (node (ref "IC6") (pin "33") (pinfunction "TP_DOUT_33") (pintype "bidirectional"))
    )
    (net (code "137") (name "SPI2_MOSI") (class "Default")
      (node (ref "IC5") (pin "54") (pinfunction "P15_54") (pintype "bidirectional"))
      (node (ref "IC6") (pin "31") (pinfunction "TP_DIN_31") (pintype "bidirectional"))
    )
    (net (code "138") (name "SPI2_SCK") (class "Default")
      (node (ref "IC5") (pin "71") (pinfunction "P12_71") (pintype "bidirectional"))
      (node (ref "IC6") (pin "29") (pinfunction "TP_CLK_29") (pintype "bidirectional"))
    )
    (net (code "139") (name "SPI3_MISO") (class "Default")
      (node (ref "IC5") (pin "79") (pinfunction "P11_79") (pintype "bidirectional"))
      (node (ref "RN10") (pin "4") (pinfunction "1_4") (pintype "passive"))
    )
    (net (code "140") (name "SPI3_MOSI") (class "Default")
      (node (ref "IC5") (pin "80") (pinfunction "P12_80") (pintype "bidirectional"))
      (node (ref "RN10") (pin "3") (pinfunction "1_3") (pintype "passive"))
    )
    (net (code "141") (name "SPI3_SCK") (class "Default")
      (node (ref "IC5") (pin "78") (pinfunction "P10_78") (pintype "bidirectional"))
      (node (ref "RN10") (pin "2") (pinfunction "1_2") (pintype "passive"))
    )
    (net (code "142") (name "SRST") (class "Default")
      (node (ref "C14") (pin "1") (pinfunction "1_1") (pintype "passive"))
      (node (ref "IC2") (pin "15") (pinfunction "ACBUS0_15") (pintype "bidirectional"))
      (node (ref "IC5") (pin "14") (pinfunction "~{RST}_14") (pintype "input"))
      (node (ref "RESET1") (pin "3") (pinfunction "3_3") (pintype "bidirectional"))
      (node (ref "RESET1") (pin "4") (pinfunction "4_4") (pintype "bidirectional"))
      (node (ref "RN1") (pin "4") (pinfunction "1_4") (pintype "passive"))
    )
    (net (code "143") (name "SWCLK") (class "Default")
      (node (ref "IC5") (pin "76") (pinfunction "P14_76") (pintype "bidirectional"))
      (node (ref "RN2") (pin "6") (pinfunction "2_6") (pintype "passive"))
    )
    (net (code "144") (name "SWCLK1") (class "Default")
      (node (ref "IC2") (pin "24") (pinfunction "ADBUS0_24") (pintype "bidirectional"))
      (node (ref "RN1") (pin "3") (pinfunction "1_3") (pintype "passive"))
      (node (ref "RN2") (pin "3") (pinfunction "1_3") (pintype "passive"))
    )
    (net (code "145") (name "SWDIO") (class "Default")
      (node (ref "IC5") (pin "72") (pinfunction "P13_72") (pintype "bidirectional"))
      (node (ref "RN2") (pin "5") (pinfunction "2_5") (pintype "passive"))
      (node (ref "RN2") (pin "8") (pinfunction "2_8") (pintype "passive"))
    )
    (net (code "146") (name "SWDIO_OE") (class "Default")
      (node (ref "IC1") (pin "1") (pinfunction "OE_1") (pintype "input"))
      (node (ref "IC2") (pin "21") (pinfunction "ADBUS3_21") (pintype "bidirectional"))
      (node (ref "RN1") (pin "1") (pinfunction "1_1") (pintype "passive"))
    )
    (net (code "147") (name "TP_CS") (class "Default")
      (node (ref "IC5") (pin "63") (pinfunction "P6_63") (pintype "bidirectional"))
      (node (ref "IC6") (pin "30") (pinfunction "TP_CS_30") (pintype "bidirectional"))
    )
    (net (code "148") (name "TP_IRQ") (class "Default")
      (node (ref "IC5") (pin "59") (pinfunction "P12_59") (pintype "bidirectional"))
      (node (ref "IC6") (pin "34") (pinfunction "TP_IRQ_34") (pintype "bidirectional"))
    )
    (net (code "149") (name "USART1_RX") (class "Default")
      (node (ref "IC5") (pin "93") (pinfunction "P7_93") (pintype "bidirectional"))
      (node (ref "RN3") (pin "5") (pinfunction "2_5") (pintype "passive"))
    )
    (net (code "150") (name "USART1_TX") (class "Default")
      (node (ref "IC5") (pin "92") (pinfunction "P6_92") (pintype "bidirectional"))
      (node (ref "RN3") (pin "8") (pinfunction "2_8") (pintype "passive"))
    )
    (net (code "151") (name "WF1_BUSY") (class "Default")
      (node (ref "IC5") (pin "83") (pinfunction "P2_83") (pintype "bidirectional"))
      (node (ref "RN11") (pin "1") (pinfunction "1_1") (pintype "passive"))
    )
    (net (code "152") (name "WF1_CS") (class "Default")
      (node (ref "IC5") (pin "87") (pinfunction "P6_87") (pintype "bidirectional"))
      (node (ref "RN10") (pin "1") (pinfunction "1_1") (pintype "passive"))
    )
    (net (code "153") (name "WF1_IRQ") (class "Default")
      (node (ref "IC5") (pin "84") (pinfunction "P3_84") (pintype "bidirectional"))
      (node (ref "RN11") (pin "4") (pinfunction "1_4") (pintype "passive"))
    )
    (net (code "154") (name "WF_3V3") (class "Default")
      (node (ref "C57") (pin "1") (pinfunction "1_1") (pintype "passive"))
      (node (ref "IC10") (pin "5") (pinfunction "VOUT_5") (pintype "passive"))
      (node (ref "L4") (pin "1") (pinfunction "1_1") (pintype "passive"))
      (node (ref "L5") (pin "1") (pinfunction "1_1") (pintype "passive"))
      (node (ref "R22") (pin "2") (pinfunction "2_2") (pintype "passive"))
    )
    (net (code "155") (name "WF_ANT") (class "Default")
      (node (ref "IC5") (pin "5") (pinfunction "P6_5") (pintype "bidirectional"))
      (node (ref "RN12") (pin "1") (pinfunction "1_1") (pintype "passive"))
    )
    (net (code "156") (name "WF_CPS") (class "Default")
      (node (ref "IC5") (pin "1") (pinfunction "P2_1") (pintype "bidirectional"))
      (node (ref "RN12") (pin "3") (pinfunction "1_3") (pintype "passive"))
    )
    (net (code "157") (name "WF_CRX") (class "Default")
      (node (ref "IC5") (pin "3") (pinfunction "P4_3") (pintype "bidirectional"))
      (node (ref "RN12") (pin "2") (pinfunction "1_2") (pintype "passive"))
    )
    (net (code "158") (name "WF_CTX") (class "Default")
      (node (ref "IC5") (pin "2") (pinfunction "P3_2") (pintype "bidirectional"))
      (node (ref "RN12") (pin "4") (pinfunction "1_4") (pintype "passive"))
    )
    (net (code "159") (name "WF_ON") (class "Default")
      (node (ref "IC10") (pin "3") (pinfunction "ON_3") (pintype "bidirectional"))
      (node (ref "IC5") (pin "91") (pinfunction "P5_91") (pintype "bidirectional"))
    )
    (net (code "160") (name "unconnected-(IC2-ACBUS1-Pad13)") (class "Default")
      (node (ref "IC2") (pin "13") (pinfunction "ACBUS1_13") (pintype "bidirectional"))
    )
    (net (code "161") (name "unconnected-(IC2-ACBUS2-Pad12)") (class "Default")
      (node (ref "IC2") (pin "12") (pinfunction "ACBUS2_12") (pintype "bidirectional"))
    )
    (net (code "162") (name "unconnected-(IC2-ACBUS3-Pad11)") (class "Default")
      (node (ref "IC2") (pin "11") (pinfunction "ACBUS3_11") (pintype "bidirectional"))
    )
    (net (code "163") (name "unconnected-(IC2-ADBUS4-Pad20)") (class "Default")
      (node (ref "IC2") (pin "20") (pinfunction "ADBUS4_20") (pintype "bidirectional"))
    )
    (net (code "164") (name "unconnected-(IC2-ADBUS5-Pad19)") (class "Default")
      (node (ref "IC2") (pin "19") (pinfunction "ADBUS5_19") (pintype "bidirectional"))
    )
    (net (code "165") (name "unconnected-(IC2-ADBUS6-Pad17)") (class "Default")
      (node (ref "IC2") (pin "17") (pinfunction "ADBUS6_17") (pintype "bidirectional"))
    )
    (net (code "166") (name "unconnected-(IC2-ADBUS7-Pad16)") (class "Default")
      (node (ref "IC2") (pin "16") (pinfunction "ADBUS7_16") (pintype "bidirectional"))
    )
    (net (code "167") (name "unconnected-(IC2-BCBUS0-Pad30)") (class "Default")
      (node (ref "IC2") (pin "30") (pinfunction "BCBUS0_30") (pintype "bidirectional"))
    )
    (net (code "168") (name "unconnected-(IC2-BCBUS1-Pad29)") (class "Default")
      (node (ref "IC2") (pin "29") (pinfunction "BCBUS1_29") (pintype "bidirectional"))
    )
    (net (code "169") (name "unconnected-(IC2-BCBUS2-Pad28)") (class "Default")
      (node (ref "IC2") (pin "28") (pinfunction "BCBUS2_28") (pintype "bidirectional"))
    )
    (net (code "170") (name "unconnected-(IC2-BCBUS3-Pad27)") (class "Default")
      (node (ref "IC2") (pin "27") (pinfunction "BCBUS3_27") (pintype "bidirectional"))
    )
    (net (code "171") (name "unconnected-(IC2-BDBUS2-Pad38)") (class "Default")
      (node (ref "IC2") (pin "38") (pinfunction "BDBUS2_38") (pintype "bidirectional"))
    )
    (net (code "172") (name "unconnected-(IC2-BDBUS3-Pad37)") (class "Default")
      (node (ref "IC2") (pin "37") (pinfunction "BDBUS3_37") (pintype "bidirectional"))
    )
    (net (code "173") (name "unconnected-(IC2-BDBUS4-Pad36)") (class "Default")
      (node (ref "IC2") (pin "36") (pinfunction "BDBUS4_36") (pintype "bidirectional"))
    )
    (net (code "174") (name "unconnected-(IC2-BDBUS5-Pad35)") (class "Default")
      (node (ref "IC2") (pin "35") (pinfunction "BDBUS5_35") (pintype "bidirectional"))
    )
    (net (code "175") (name "unconnected-(IC2-BDBUS6-Pad33)") (class "Default")
      (node (ref "IC2") (pin "33") (pinfunction "BDBUS6_33") (pintype "bidirectional"))
    )
    (net (code "176") (name "unconnected-(IC2-BDBUS7-Pad32)") (class "Default")
      (node (ref "IC2") (pin "32") (pinfunction "BDBUS7_32") (pintype "bidirectional"))
    )
    (net (code "177") (name "unconnected-(IC2-PWREN-Pad41)") (class "Default")
      (node (ref "IC2") (pin "41") (pinfunction "PWREN_41") (pintype "bidirectional"))
    )
    (net (code "178") (name "unconnected-(IC5A-P8-Pad67)") (class "Default")
      (node (ref "IC5") (pin "67") (pinfunction "P8_67") (pintype "bidirectional"))
    )
    (net (code "179") (name "unconnected-(IC5A-P11-Pad70)") (class "Default")
      (node (ref "IC5") (pin "70") (pinfunction "P11_70") (pintype "bidirectional"))
    )
    (net (code "180") (name "unconnected-(IC5C-P2-Pad36)") (class "Default")
      (node (ref "IC5") (pin "36") (pinfunction "P2_36") (pintype "bidirectional"))
    )
    (net (code "181") (name "unconnected-(IC5C-P4-Pad90)") (class "Default")
      (node (ref "IC5") (pin "90") (pinfunction "P4_90") (pintype "bidirectional"))
    )
    (net (code "182") (name "unconnected-(IC5C-P9-Pad96)") (class "Default")
      (node (ref "IC5") (pin "96") (pinfunction "P9_96") (pintype "bidirectional"))
    )
    (net (code "183") (name "unconnected-(IC5D-P0-Pad15)") (class "Default")
      (node (ref "IC5") (pin "15") (pinfunction "P0_15") (pintype "bidirectional"))
    )
    (net (code "184") (name "unconnected-(IC5D-P7-Pad64)") (class "Default")
      (node (ref "IC5") (pin "64") (pinfunction "P7_64") (pintype "bidirectional"))
    )
    (net (code "185") (name "unconnected-(IC5D-P8-Pad65)") (class "Default")
      (node (ref "IC5") (pin "65") (pinfunction "P8_65") (pintype "bidirectional"))
    )
    (net (code "186") (name "unconnected-(IC5D-P9-Pad66)") (class "Default")
      (node (ref "IC5") (pin "66") (pinfunction "P9_66") (pintype "bidirectional"))
    )
    (net (code "187") (name "unconnected-(IC5D-P13-Pad7)") (class "Default")
      (node (ref "IC5") (pin "7") (pinfunction "P13_7") (pintype "bidirectional"))
    )
    (net (code "188") (name "unconnected-(IC5E-P13-Pad60)") (class "Default")
      (node (ref "IC5") (pin "60") (pinfunction "P13_60") (pintype "bidirectional"))
    )
    (net (code "189") (name "unconnected-(IC5G-P0-Pad97)") (class "Default")
      (node (ref "IC5") (pin "97") (pinfunction "P0_97") (pintype "bidirectional"))
    )
    (net (code "190") (name "unconnected-(IC5G-P1-Pad98)") (class "Default")
      (node (ref "IC5") (pin "98") (pinfunction "P1_98") (pintype "bidirectional"))
    )
    (net (code "191") (name "unconnected-(IC5H-OSC_OUT-Pad13)") (class "Default")
      (node (ref "IC5") (pin "13") (pinfunction "OSC_OUT_13") (pintype "passive"))
    )
    (net (code "192") (name "unconnected-(IC6-F_CS-Pad16)") (class "Default")
      (node (ref "IC6") (pin "16") (pinfunction "F_CS_16") (pintype "bidirectional"))
    )
    (net (code "193") (name "unconnected-(IC6-SD_CLK-Pad36)") (class "Default")
      (node (ref "IC6") (pin "36") (pinfunction "SD_CLK_36") (pintype "bidirectional"))
    )
    (net (code "194") (name "unconnected-(IC6-SD_CS-Pad38)") (class "Default")
      (node (ref "IC6") (pin "38") (pinfunction "SD_CS_38") (pintype "bidirectional"))
    )
    (net (code "195") (name "unconnected-(IC6-SD_DIN-Pad37)") (class "Default")
      (node (ref "IC6") (pin "37") (pinfunction "SD_DIN_37") (pintype "bidirectional"))
    )
    (net (code "196") (name "unconnected-(IC6-SD_DO-Pad35)") (class "Default")
      (node (ref "IC6") (pin "35") (pinfunction "SD_DO_35") (pintype "bidirectional"))
    )
    (net (code "197") (name "unconnected-(IC7-NC-Pad8)") (class "Default")
      (node (ref "IC7") (pin "8") (pinfunction "NC_8") (pintype "bidirectional"))
    )
    (net (code "198") (name "unconnected-(IC7-NC-Pad9)") (class "Default")
      (node (ref "IC7") (pin "9") (pinfunction "NC_9") (pintype "bidirectional"))
    )
    (net (code "199") (name "unconnected-(IC7-NC-Pad10)") (class "Default")
      (node (ref "IC7") (pin "10") (pinfunction "NC_10") (pintype "bidirectional"))
    )
    (net (code "200") (name "unconnected-(IC7-NC-Pad11)") (class "Default")
      (node (ref "IC7") (pin "11") (pinfunction "NC_11") (pintype "bidirectional"))
    )
    (net (code "201") (name "unconnected-(IC7-NC-Pad12)") (class "Default")
      (node (ref "IC7") (pin "12") (pinfunction "NC_12") (pintype "bidirectional"))
    )
    (net (code "202") (name "unconnected-(IC7-X2-Pad33)") (class "Default")
      (node (ref "IC7") (pin "33") (pinfunction "X2_33") (pintype "bidirectional"))
    )
    (net (code "203") (name "unconnected-(IC9-DCC_SW-Pad14)") (class "Default")
      (node (ref "IC9") (pin "14") (pinfunction "DCC_SW_14") (pintype "bidirectional"))
    )
    (net (code "204") (name "unconnected-(IC9-DIO2-Pad9)") (class "Default")
      (node (ref "IC9") (pin "9") (pinfunction "DIO2_9") (pintype "bidirectional"))
    )
    (net (code "205") (name "unconnected-(IC9-DIO3-Pad10)") (class "Default")
      (node (ref "IC9") (pin "10") (pinfunction "DIO3_10") (pintype "bidirectional"))
    )
    (net (code "206") (name "unconnected-(RN2B-1-Pad2)") (class "Default")
      (node (ref "RN2") (pin "2") (pinfunction "1_2") (pintype "passive"))
    )
    (net (code "207") (name "unconnected-(RN2B-2-Pad7)") (class "Default")
      (node (ref "RN2") (pin "7") (pinfunction "2_7") (pintype "passive"))
    )
    (net (code "208") (name "unconnected-(RN3B-1-Pad2)") (class "Default")
      (node (ref "RN3") (pin "2") (pinfunction "1_2") (pintype "passive"))
    )
    (net (code "209") (name "unconnected-(RN3B-2-Pad7)") (class "Default")
      (node (ref "RN3") (pin "7") (pinfunction "2_7") (pintype "passive"))
    )
    (net (code "210") (name "unconnected-(RN3C-1-Pad3)") (class "Default")
      (node (ref "RN3") (pin "3") (pinfunction "1_3") (pintype "passive"))
    )
    (net (code "211") (name "unconnected-(RN3C-2-Pad6)") (class "Default")
      (node (ref "RN3") (pin "6") (pinfunction "2_6") (pintype "passive"))
    )
    (net (code "212") (name "unconnected-(RN7D-1-Pad4)") (class "Default")
      (node (ref "RN7") (pin "4") (pinfunction "1_4") (pintype "passive"))
    )
    (net (code "213") (name "unconnected-(RN9-Pad1)") (class "Default")
      (node (ref "RN9") (pin "1") (pinfunction "1_1") (pintype "passive"))
    )
    (net (code "214") (name "unconnected-(RN9A-2-Pad8)") (class "Default")
      (node (ref "RN9") (pin "8") (pinfunction "2_8") (pintype "passive"))
    )
    (net (code "215") (name "unconnected-(RN11B-1-Pad2)") (class "Default")
      (node (ref "RN11") (pin "2") (pinfunction "1_2") (pintype "passive"))
    )
    (net (code "216") (name "unconnected-(RN11B-2-Pad7)") (class "Default")
      (node (ref "RN11") (pin "7") (pinfunction "2_7") (pintype "passive"))
    )
    (net (code "217") (name "unconnected-(RN11C-1-Pad3)") (class "Default")
      (node (ref "RN11") (pin "3") (pinfunction "1_3") (pintype "passive"))
    )
    (net (code "218") (name "unconnected-(RN11C-2-Pad6)") (class "Default")
      (node (ref "RN11") (pin "6") (pinfunction "2_6") (pintype "passive"))
    )
    (net (code "219") (name "unconnected-(USB1-ID-Pad4)") (class "Default")
      (node (ref "USB1") (pin "4") (pinfunction "ID_4") (pintype "bidirectional"))
    )
  )
)
